# lighting_ctl.net
KiCad netlist of a schematic drawn in EAGLE
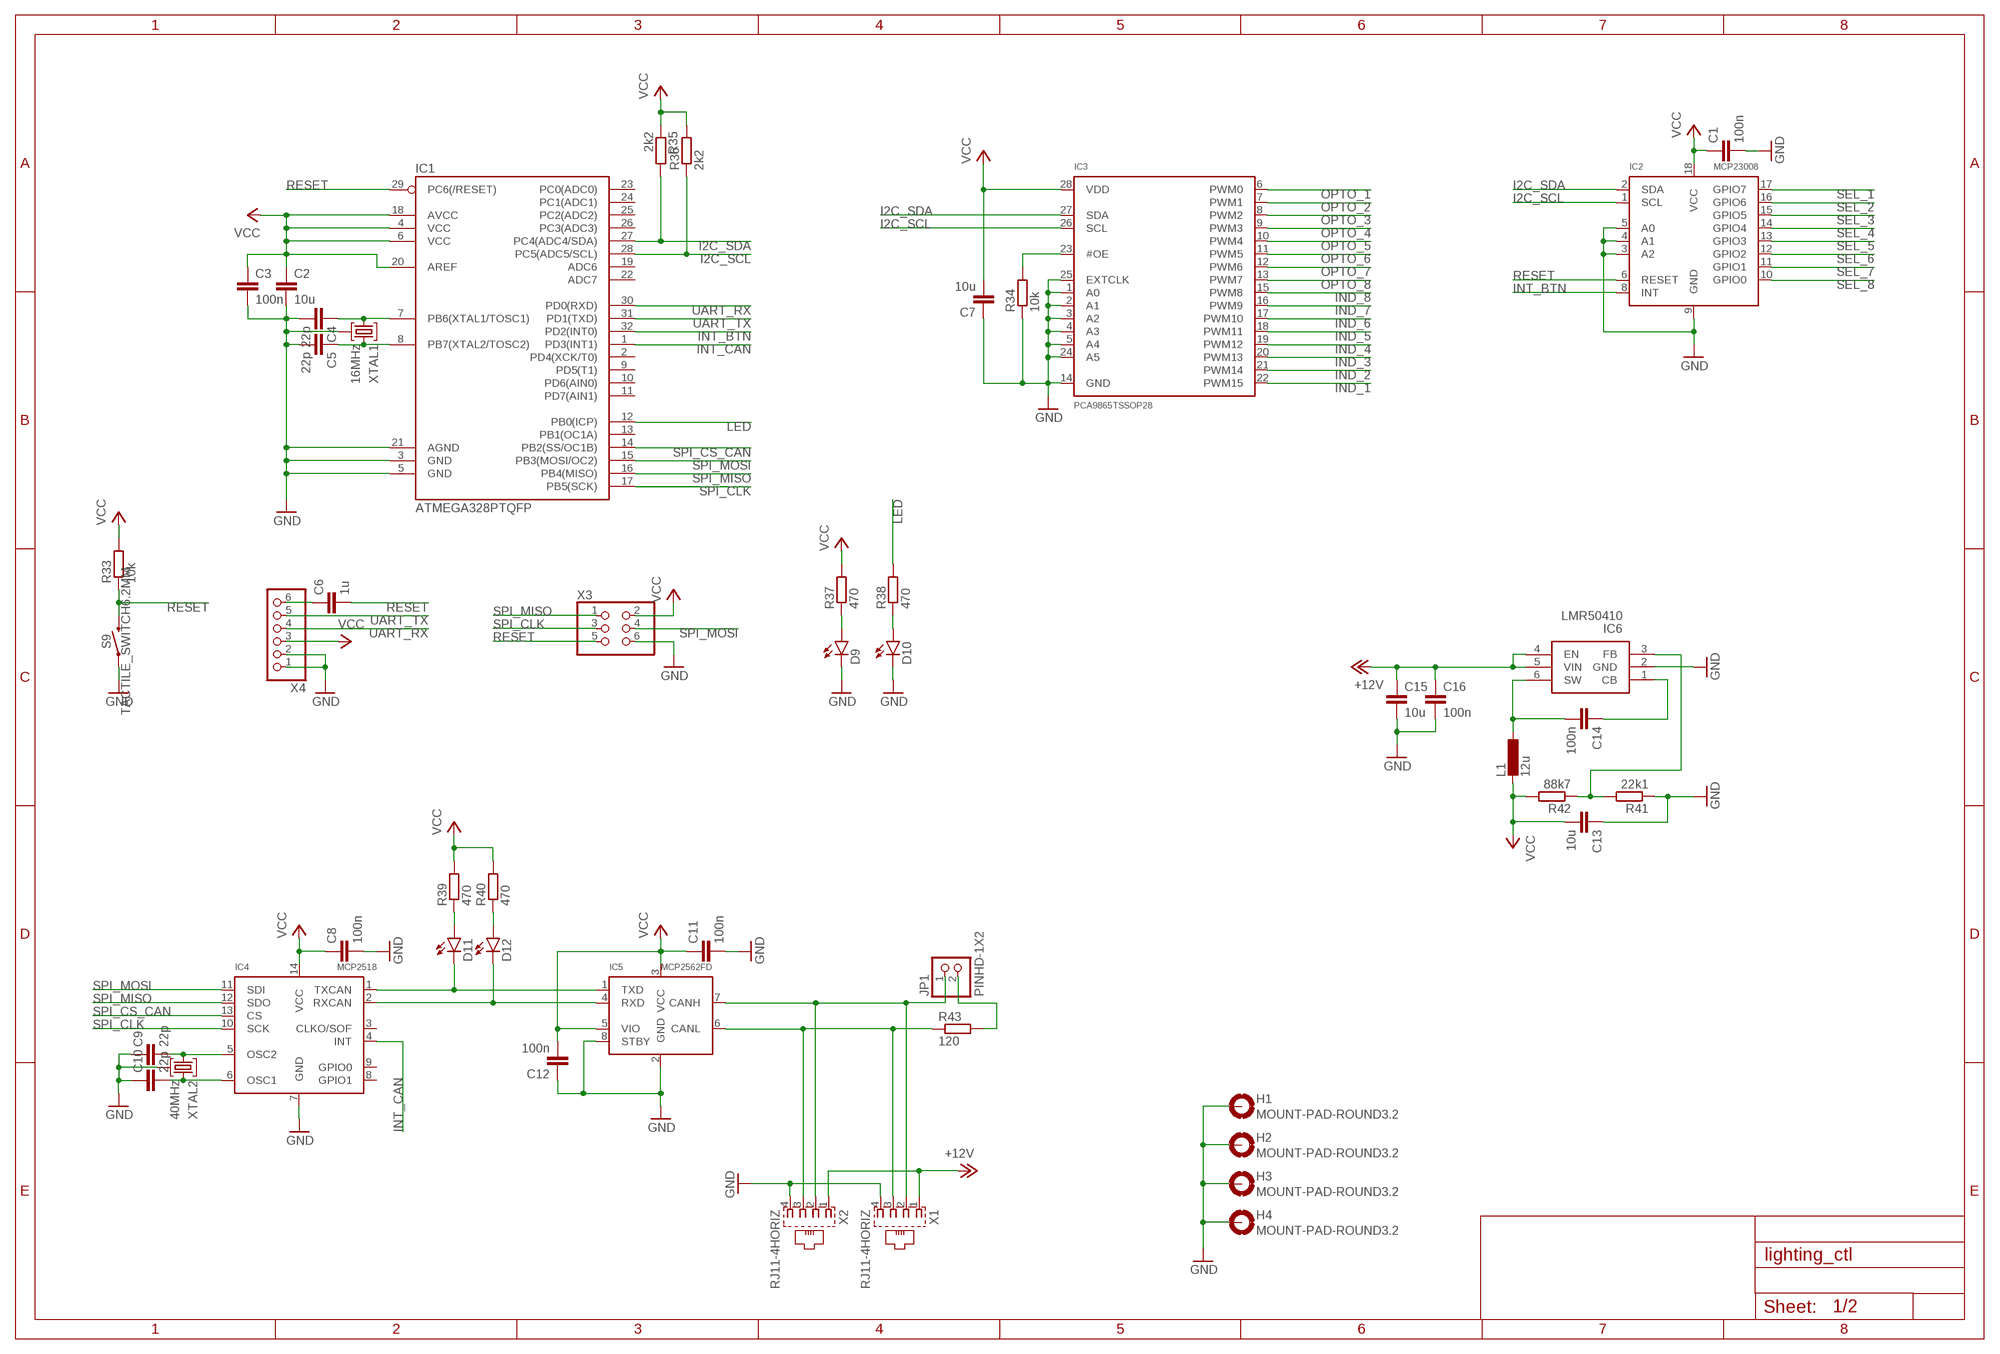
[diagram p0: schematic, sheet 1]
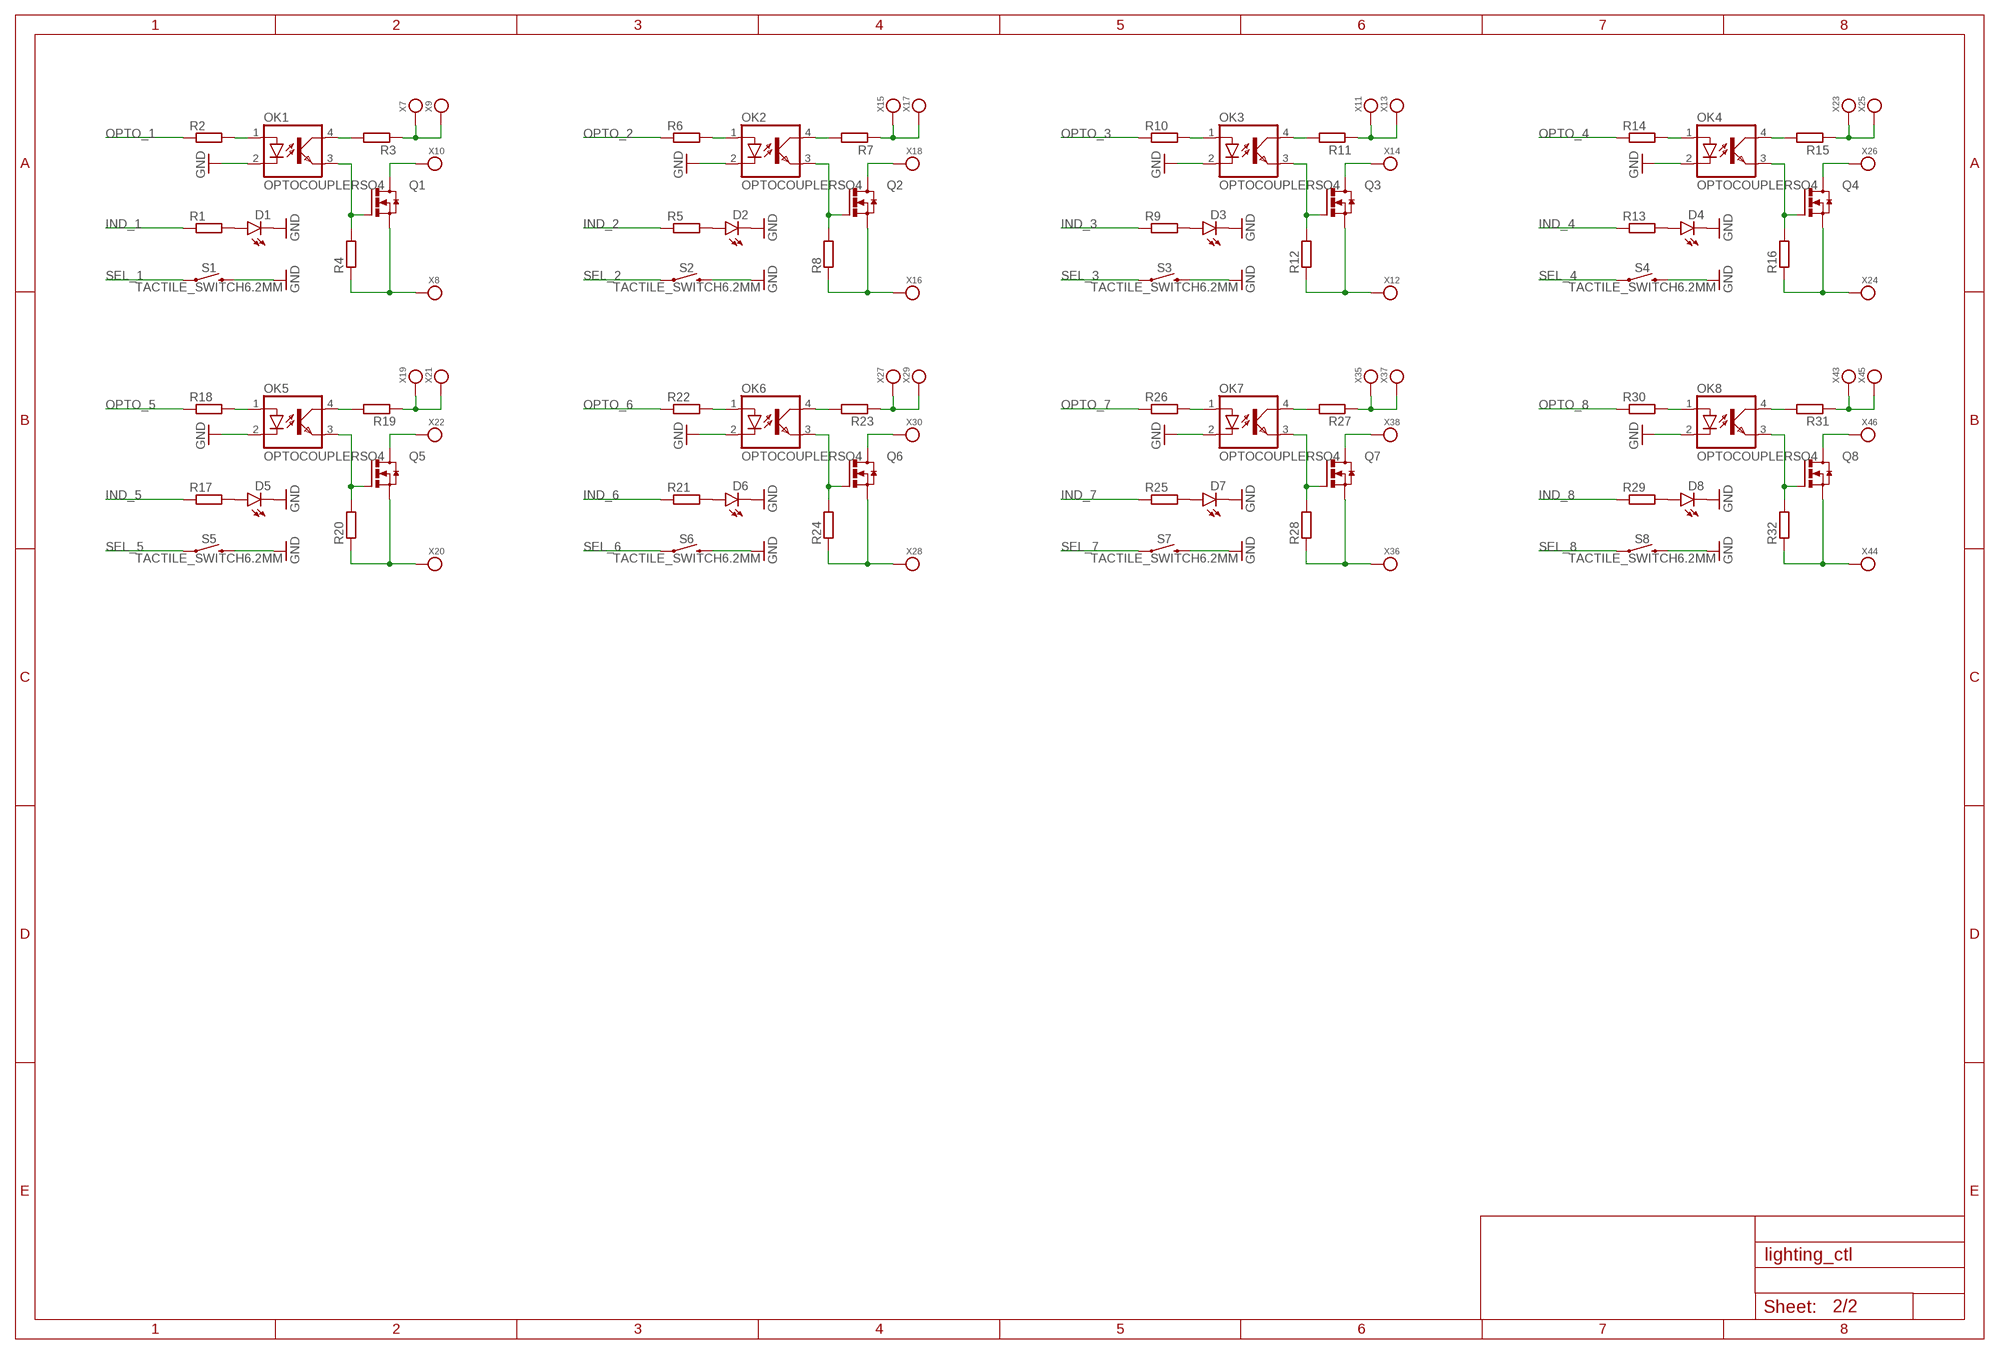
[diagram p1: schematic, sheet 2]

(export (version "E")
  (design (tool "Eeschema 10.0.6"))
  (components
    (comp (ref "D1")
      (value "LED1206")
      (footprint "eagle-import:CHIPLED_1206")
      (libsource (lib "eagle-import") (part "LED1206"))
    )
    (comp (ref "D2")
      (value "LED1206")
      (footprint "eagle-import:CHIPLED_1206")
      (libsource (lib "eagle-import") (part "LED1206"))
    )
    (comp (ref "D3")
      (value "LED1206")
      (footprint "eagle-import:CHIPLED_1206")
      (libsource (lib "eagle-import") (part "LED1206"))
    )
    (comp (ref "D4")
      (value "LED1206")
      (footprint "eagle-import:CHIPLED_1206")
      (libsource (lib "eagle-import") (part "LED1206"))
    )
    (comp (ref "D5")
      (value "LED1206")
      (footprint "eagle-import:CHIPLED_1206")
      (libsource (lib "eagle-import") (part "LED1206"))
    )
    (comp (ref "D6")
      (value "LED1206")
      (footprint "eagle-import:CHIPLED_1206")
      (libsource (lib "eagle-import") (part "LED1206"))
    )
    (comp (ref "D7")
      (value "LED1206")
      (footprint "eagle-import:CHIPLED_1206")
      (libsource (lib "eagle-import") (part "LED1206"))
    )
    (comp (ref "D8")
      (value "LED1206")
      (footprint "eagle-import:CHIPLED_1206")
      (libsource (lib "eagle-import") (part "LED1206"))
    )
    (comp (ref "OK1")
      (value "OPTOCOUPLERSO4")
      (footprint "eagle-import:SO04")
      (libsource (lib "eagle-import") (part "OPTOCOUPLERSO4"))
    )
    (comp (ref "OK2")
      (value "OPTOCOUPLERSO4")
      (footprint "eagle-import:SO04")
      (libsource (lib "eagle-import") (part "OPTOCOUPLERSO4"))
    )
    (comp (ref "OK3")
      (value "OPTOCOUPLERSO4")
      (footprint "eagle-import:SO04")
      (libsource (lib "eagle-import") (part "OPTOCOUPLERSO4"))
    )
    (comp (ref "OK4")
      (value "OPTOCOUPLERSO4")
      (footprint "eagle-import:SO04")
      (libsource (lib "eagle-import") (part "OPTOCOUPLERSO4"))
    )
    (comp (ref "OK5")
      (value "OPTOCOUPLERSO4")
      (footprint "eagle-import:SO04")
      (libsource (lib "eagle-import") (part "OPTOCOUPLERSO4"))
    )
    (comp (ref "OK6")
      (value "OPTOCOUPLERSO4")
      (footprint "eagle-import:SO04")
      (libsource (lib "eagle-import") (part "OPTOCOUPLERSO4"))
    )
    (comp (ref "OK7")
      (value "OPTOCOUPLERSO4")
      (footprint "eagle-import:SO04")
      (libsource (lib "eagle-import") (part "OPTOCOUPLERSO4"))
    )
    (comp (ref "OK8")
      (value "OPTOCOUPLERSO4")
      (footprint "eagle-import:SO04")
      (libsource (lib "eagle-import") (part "OPTOCOUPLERSO4"))
    )
    (comp (ref "Q1")
      (value "MOSFET_N_CHANNELSOT223")
      (footprint "eagle-import:SOT223")
      (libsource (lib "eagle-import") (part "MOSFET_N_CHANNELSOT223"))
    )
    (comp (ref "Q2")
      (value "MOSFET_N_CHANNELSOT223")
      (footprint "eagle-import:SOT223")
      (libsource (lib "eagle-import") (part "MOSFET_N_CHANNELSOT223"))
    )
    (comp (ref "Q3")
      (value "MOSFET_N_CHANNELSOT223")
      (footprint "eagle-import:SOT223")
      (libsource (lib "eagle-import") (part "MOSFET_N_CHANNELSOT223"))
    )
    (comp (ref "Q4")
      (value "MOSFET_N_CHANNELSOT223")
      (footprint "eagle-import:SOT223")
      (libsource (lib "eagle-import") (part "MOSFET_N_CHANNELSOT223"))
    )
    (comp (ref "Q5")
      (value "MOSFET_N_CHANNELSOT223")
      (footprint "eagle-import:SOT223")
      (libsource (lib "eagle-import") (part "MOSFET_N_CHANNELSOT223"))
    )
    (comp (ref "Q6")
      (value "MOSFET_N_CHANNELSOT223")
      (footprint "eagle-import:SOT223")
      (libsource (lib "eagle-import") (part "MOSFET_N_CHANNELSOT223"))
    )
    (comp (ref "Q7")
      (value "MOSFET_N_CHANNELSOT223")
      (footprint "eagle-import:SOT223")
      (libsource (lib "eagle-import") (part "MOSFET_N_CHANNELSOT223"))
    )
    (comp (ref "Q8")
      (value "MOSFET_N_CHANNELSOT223")
      (footprint "eagle-import:SOT223")
      (libsource (lib "eagle-import") (part "MOSFET_N_CHANNELSOT223"))
    )
    (comp (ref "R1")
      (value "RESISTOR0805")
      (footprint "eagle-import:R0805")
      (libsource (lib "eagle-import") (part "RESISTOR0805"))
    )
    (comp (ref "R2")
      (value "RESISTOR0805")
      (footprint "eagle-import:R0805")
      (libsource (lib "eagle-import") (part "RESISTOR0805"))
    )
    (comp (ref "R3")
      (value "RESISTOR0805")
      (footprint "eagle-import:R0805")
      (libsource (lib "eagle-import") (part "RESISTOR0805"))
    )
    (comp (ref "R4")
      (value "RESISTOR0805")
      (footprint "eagle-import:R0805")
      (libsource (lib "eagle-import") (part "RESISTOR0805"))
    )
    (comp (ref "R5")
      (value "RESISTOR0805")
      (footprint "eagle-import:R0805")
      (libsource (lib "eagle-import") (part "RESISTOR0805"))
    )
    (comp (ref "R6")
      (value "RESISTOR0805")
      (footprint "eagle-import:R0805")
      (libsource (lib "eagle-import") (part "RESISTOR0805"))
    )
    (comp (ref "R7")
      (value "RESISTOR0805")
      (footprint "eagle-import:R0805")
      (libsource (lib "eagle-import") (part "RESISTOR0805"))
    )
    (comp (ref "R8")
      (value "RESISTOR0805")
      (footprint "eagle-import:R0805")
      (libsource (lib "eagle-import") (part "RESISTOR0805"))
    )
    (comp (ref "R9")
      (value "RESISTOR0805")
      (footprint "eagle-import:R0805")
      (libsource (lib "eagle-import") (part "RESISTOR0805"))
    )
    (comp (ref "R10")
      (value "RESISTOR0805")
      (footprint "eagle-import:R0805")
      (libsource (lib "eagle-import") (part "RESISTOR0805"))
    )
    (comp (ref "R11")
      (value "RESISTOR0805")
      (footprint "eagle-import:R0805")
      (libsource (lib "eagle-import") (part "RESISTOR0805"))
    )
    (comp (ref "R12")
      (value "RESISTOR0805")
      (footprint "eagle-import:R0805")
      (libsource (lib "eagle-import") (part "RESISTOR0805"))
    )
    (comp (ref "R13")
      (value "RESISTOR0805")
      (footprint "eagle-import:R0805")
      (libsource (lib "eagle-import") (part "RESISTOR0805"))
    )
    (comp (ref "R14")
      (value "RESISTOR0805")
      (footprint "eagle-import:R0805")
      (libsource (lib "eagle-import") (part "RESISTOR0805"))
    )
    (comp (ref "R15")
      (value "RESISTOR0805")
      (footprint "eagle-import:R0805")
      (libsource (lib "eagle-import") (part "RESISTOR0805"))
    )
    (comp (ref "R16")
      (value "RESISTOR0805")
      (footprint "eagle-import:R0805")
      (libsource (lib "eagle-import") (part "RESISTOR0805"))
    )
    (comp (ref "R17")
      (value "RESISTOR0805")
      (footprint "eagle-import:R0805")
      (libsource (lib "eagle-import") (part "RESISTOR0805"))
    )
    (comp (ref "R18")
      (value "RESISTOR0805")
      (footprint "eagle-import:R0805")
      (libsource (lib "eagle-import") (part "RESISTOR0805"))
    )
    (comp (ref "R19")
      (value "RESISTOR0805")
      (footprint "eagle-import:R0805")
      (libsource (lib "eagle-import") (part "RESISTOR0805"))
    )
    (comp (ref "R20")
      (value "RESISTOR0805")
      (footprint "eagle-import:R0805")
      (libsource (lib "eagle-import") (part "RESISTOR0805"))
    )
    (comp (ref "R21")
      (value "RESISTOR0805")
      (footprint "eagle-import:R0805")
      (libsource (lib "eagle-import") (part "RESISTOR0805"))
    )
    (comp (ref "R22")
      (value "RESISTOR0805")
      (footprint "eagle-import:R0805")
      (libsource (lib "eagle-import") (part "RESISTOR0805"))
    )
    (comp (ref "R23")
      (value "RESISTOR0805")
      (footprint "eagle-import:R0805")
      (libsource (lib "eagle-import") (part "RESISTOR0805"))
    )
    (comp (ref "R24")
      (value "RESISTOR0805")
      (footprint "eagle-import:R0805")
      (libsource (lib "eagle-import") (part "RESISTOR0805"))
    )
    (comp (ref "R25")
      (value "RESISTOR0805")
      (footprint "eagle-import:R0805")
      (libsource (lib "eagle-import") (part "RESISTOR0805"))
    )
    (comp (ref "R26")
      (value "RESISTOR0805")
      (footprint "eagle-import:R0805")
      (libsource (lib "eagle-import") (part "RESISTOR0805"))
    )
    (comp (ref "R27")
      (value "RESISTOR0805")
      (footprint "eagle-import:R0805")
      (libsource (lib "eagle-import") (part "RESISTOR0805"))
    )
    (comp (ref "R28")
      (value "RESISTOR0805")
      (footprint "eagle-import:R0805")
      (libsource (lib "eagle-import") (part "RESISTOR0805"))
    )
    (comp (ref "R29")
      (value "RESISTOR0805")
      (footprint "eagle-import:R0805")
      (libsource (lib "eagle-import") (part "RESISTOR0805"))
    )
    (comp (ref "R30")
      (value "RESISTOR0805")
      (footprint "eagle-import:R0805")
      (libsource (lib "eagle-import") (part "RESISTOR0805"))
    )
    (comp (ref "R31")
      (value "RESISTOR0805")
      (footprint "eagle-import:R0805")
      (libsource (lib "eagle-import") (part "RESISTOR0805"))
    )
    (comp (ref "R32")
      (value "RESISTOR0805")
      (footprint "eagle-import:R0805")
      (libsource (lib "eagle-import") (part "RESISTOR0805"))
    )
    (comp (ref "S1")
      (value "TACTILE_SWITCH6.2MM")
      (footprint "eagle-import:TACTILE_SWITCH_SMD_6.2MM")
      (libsource (lib "eagle-import") (part "TACTILE_SWITCH6.2MM"))
    )
    (comp (ref "S2")
      (value "TACTILE_SWITCH6.2MM")
      (footprint "eagle-import:TACTILE_SWITCH_SMD_6.2MM")
      (libsource (lib "eagle-import") (part "TACTILE_SWITCH6.2MM"))
    )
    (comp (ref "S3")
      (value "TACTILE_SWITCH6.2MM")
      (footprint "eagle-import:TACTILE_SWITCH_SMD_6.2MM")
      (libsource (lib "eagle-import") (part "TACTILE_SWITCH6.2MM"))
    )
    (comp (ref "S4")
      (value "TACTILE_SWITCH6.2MM")
      (footprint "eagle-import:TACTILE_SWITCH_SMD_6.2MM")
      (libsource (lib "eagle-import") (part "TACTILE_SWITCH6.2MM"))
    )
    (comp (ref "S5")
      (value "TACTILE_SWITCH6.2MM")
      (footprint "eagle-import:TACTILE_SWITCH_SMD_6.2MM")
      (libsource (lib "eagle-import") (part "TACTILE_SWITCH6.2MM"))
    )
    (comp (ref "S6")
      (value "TACTILE_SWITCH6.2MM")
      (footprint "eagle-import:TACTILE_SWITCH_SMD_6.2MM")
      (libsource (lib "eagle-import") (part "TACTILE_SWITCH6.2MM"))
    )
    (comp (ref "S7")
      (value "TACTILE_SWITCH6.2MM")
      (footprint "eagle-import:TACTILE_SWITCH_SMD_6.2MM")
      (libsource (lib "eagle-import") (part "TACTILE_SWITCH6.2MM"))
    )
    (comp (ref "S8")
      (value "TACTILE_SWITCH6.2MM")
      (footprint "eagle-import:TACTILE_SWITCH_SMD_6.2MM")
      (libsource (lib "eagle-import") (part "TACTILE_SWITCH6.2MM"))
    )
    (comp (ref "X7")
      (value "KEYSTONE_7788")
      (footprint "eagle-import:KEYSTONE_7788")
      (libsource (lib "eagle-import") (part "KEYSTONE_7788"))
    )
    (comp (ref "X8")
      (value "KEYSTONE_7788")
      (footprint "eagle-import:KEYSTONE_7788")
      (libsource (lib "eagle-import") (part "KEYSTONE_7788"))
    )
    (comp (ref "X9")
      (value "KEYSTONE_7788")
      (footprint "eagle-import:KEYSTONE_7788")
      (libsource (lib "eagle-import") (part "KEYSTONE_7788"))
    )
    (comp (ref "X10")
      (value "KEYSTONE_7788")
      (footprint "eagle-import:KEYSTONE_7788")
      (libsource (lib "eagle-import") (part "KEYSTONE_7788"))
    )
    (comp (ref "X11")
      (value "KEYSTONE_7788")
      (footprint "eagle-import:KEYSTONE_7788")
      (libsource (lib "eagle-import") (part "KEYSTONE_7788"))
    )
    (comp (ref "X12")
      (value "KEYSTONE_7788")
      (footprint "eagle-import:KEYSTONE_7788")
      (libsource (lib "eagle-import") (part "KEYSTONE_7788"))
    )
    (comp (ref "X13")
      (value "KEYSTONE_7788")
      (footprint "eagle-import:KEYSTONE_7788")
      (libsource (lib "eagle-import") (part "KEYSTONE_7788"))
    )
    (comp (ref "X14")
      (value "KEYSTONE_7788")
      (footprint "eagle-import:KEYSTONE_7788")
      (libsource (lib "eagle-import") (part "KEYSTONE_7788"))
    )
    (comp (ref "X15")
      (value "KEYSTONE_7788")
      (footprint "eagle-import:KEYSTONE_7788")
      (libsource (lib "eagle-import") (part "KEYSTONE_7788"))
    )
    (comp (ref "X16")
      (value "KEYSTONE_7788")
      (footprint "eagle-import:KEYSTONE_7788")
      (libsource (lib "eagle-import") (part "KEYSTONE_7788"))
    )
    (comp (ref "X17")
      (value "KEYSTONE_7788")
      (footprint "eagle-import:KEYSTONE_7788")
      (libsource (lib "eagle-import") (part "KEYSTONE_7788"))
    )
    (comp (ref "X18")
      (value "KEYSTONE_7788")
      (footprint "eagle-import:KEYSTONE_7788")
      (libsource (lib "eagle-import") (part "KEYSTONE_7788"))
    )
    (comp (ref "X19")
      (value "KEYSTONE_7788")
      (footprint "eagle-import:KEYSTONE_7788")
      (libsource (lib "eagle-import") (part "KEYSTONE_7788"))
    )
    (comp (ref "X20")
      (value "KEYSTONE_7788")
      (footprint "eagle-import:KEYSTONE_7788")
      (libsource (lib "eagle-import") (part "KEYSTONE_7788"))
    )
    (comp (ref "X21")
      (value "KEYSTONE_7788")
      (footprint "eagle-import:KEYSTONE_7788")
      (libsource (lib "eagle-import") (part "KEYSTONE_7788"))
    )
    (comp (ref "X22")
      (value "KEYSTONE_7788")
      (footprint "eagle-import:KEYSTONE_7788")
      (libsource (lib "eagle-import") (part "KEYSTONE_7788"))
    )
    (comp (ref "X23")
      (value "KEYSTONE_7788")
      (footprint "eagle-import:KEYSTONE_7788")
      (libsource (lib "eagle-import") (part "KEYSTONE_7788"))
    )
    (comp (ref "X24")
      (value "KEYSTONE_7788")
      (footprint "eagle-import:KEYSTONE_7788")
      (libsource (lib "eagle-import") (part "KEYSTONE_7788"))
    )
    (comp (ref "X25")
      (value "KEYSTONE_7788")
      (footprint "eagle-import:KEYSTONE_7788")
      (libsource (lib "eagle-import") (part "KEYSTONE_7788"))
    )
    (comp (ref "X26")
      (value "KEYSTONE_7788")
      (footprint "eagle-import:KEYSTONE_7788")
      (libsource (lib "eagle-import") (part "KEYSTONE_7788"))
    )
    (comp (ref "X27")
      (value "KEYSTONE_7788")
      (footprint "eagle-import:KEYSTONE_7788")
      (libsource (lib "eagle-import") (part "KEYSTONE_7788"))
    )
    (comp (ref "X28")
      (value "KEYSTONE_7788")
      (footprint "eagle-import:KEYSTONE_7788")
      (libsource (lib "eagle-import") (part "KEYSTONE_7788"))
    )
    (comp (ref "X29")
      (value "KEYSTONE_7788")
      (footprint "eagle-import:KEYSTONE_7788")
      (libsource (lib "eagle-import") (part "KEYSTONE_7788"))
    )
    (comp (ref "X30")
      (value "KEYSTONE_7788")
      (footprint "eagle-import:KEYSTONE_7788")
      (libsource (lib "eagle-import") (part "KEYSTONE_7788"))
    )
    (comp (ref "X35")
      (value "KEYSTONE_7788")
      (footprint "eagle-import:KEYSTONE_7788")
      (libsource (lib "eagle-import") (part "KEYSTONE_7788"))
    )
    (comp (ref "X36")
      (value "KEYSTONE_7788")
      (footprint "eagle-import:KEYSTONE_7788")
      (libsource (lib "eagle-import") (part "KEYSTONE_7788"))
    )
    (comp (ref "X37")
      (value "KEYSTONE_7788")
      (footprint "eagle-import:KEYSTONE_7788")
      (libsource (lib "eagle-import") (part "KEYSTONE_7788"))
    )
    (comp (ref "X38")
      (value "KEYSTONE_7788")
      (footprint "eagle-import:KEYSTONE_7788")
      (libsource (lib "eagle-import") (part "KEYSTONE_7788"))
    )
    (comp (ref "X43")
      (value "KEYSTONE_7788")
      (footprint "eagle-import:KEYSTONE_7788")
      (libsource (lib "eagle-import") (part "KEYSTONE_7788"))
    )
    (comp (ref "X44")
      (value "KEYSTONE_7788")
      (footprint "eagle-import:KEYSTONE_7788")
      (libsource (lib "eagle-import") (part "KEYSTONE_7788"))
    )
    (comp (ref "X45")
      (value "KEYSTONE_7788")
      (footprint "eagle-import:KEYSTONE_7788")
      (libsource (lib "eagle-import") (part "KEYSTONE_7788"))
    )
    (comp (ref "X46")
      (value "KEYSTONE_7788")
      (footprint "eagle-import:KEYSTONE_7788")
      (libsource (lib "eagle-import") (part "KEYSTONE_7788"))
    )
    (comp (ref "C1")
      (value "100n")
      (footprint "eagle-import:C0805")
      (libsource (lib "eagle-import") (part "CAPACITOR0805"))
    )
    (comp (ref "C2")
      (value "10u")
      (footprint "eagle-import:C1206")
      (libsource (lib "eagle-import") (part "CAPACITOR1206"))
    )
    (comp (ref "C3")
      (value "100n")
      (footprint "eagle-import:C0805")
      (libsource (lib "eagle-import") (part "CAPACITOR0805"))
    )
    (comp (ref "C4")
      (value "22p")
      (footprint "eagle-import:C0805")
      (libsource (lib "eagle-import") (part "CAPACITOR0805"))
    )
    (comp (ref "C5")
      (value "22p")
      (footprint "eagle-import:C0805")
      (libsource (lib "eagle-import") (part "CAPACITOR0805"))
    )
    (comp (ref "C6")
      (value "1u")
      (footprint "eagle-import:C0805")
      (libsource (lib "eagle-import") (part "CAPACITOR0805"))
    )
    (comp (ref "C7")
      (value "10u")
      (footprint "eagle-import:C1206")
      (libsource (lib "eagle-import") (part "CAPACITOR1206"))
    )
    (comp (ref "C8")
      (value "100n")
      (footprint "eagle-import:C0805")
      (libsource (lib "eagle-import") (part "CAPACITOR0805"))
    )
    (comp (ref "C9")
      (value "22p")
      (footprint "eagle-import:C0805")
      (libsource (lib "eagle-import") (part "CAPACITOR0805"))
    )
    (comp (ref "C10")
      (value "22p")
      (footprint "eagle-import:C0805")
      (libsource (lib "eagle-import") (part "CAPACITOR0805"))
    )
    (comp (ref "C11")
      (value "100n")
      (footprint "eagle-import:C0805")
      (libsource (lib "eagle-import") (part "CAPACITOR0805"))
    )
    (comp (ref "C12")
      (value "100n")
      (footprint "eagle-import:C0805")
      (libsource (lib "eagle-import") (part "CAPACITOR0805"))
    )
    (comp (ref "C13")
      (value "10u")
      (footprint "eagle-import:C1206")
      (libsource (lib "eagle-import") (part "CAPACITOR1206"))
    )
    (comp (ref "C14")
      (value "100n")
      (footprint "eagle-import:C0805")
      (libsource (lib "eagle-import") (part "CAPACITOR0805"))
    )
    (comp (ref "C15")
      (value "10u")
      (footprint "eagle-import:C1206")
      (libsource (lib "eagle-import") (part "CAPACITOR1206"))
    )
    (comp (ref "C16")
      (value "100n")
      (footprint "eagle-import:C0805")
      (libsource (lib "eagle-import") (part "CAPACITOR0805"))
    )
    (comp (ref "D9")
      (value "LED1206")
      (footprint "eagle-import:CHIPLED_1206")
      (libsource (lib "eagle-import") (part "LED1206"))
    )
    (comp (ref "D10")
      (value "LED1206")
      (footprint "eagle-import:CHIPLED_1206")
      (libsource (lib "eagle-import") (part "LED1206"))
    )
    (comp (ref "D11")
      (value "LED1206")
      (footprint "eagle-import:CHIPLED_1206")
      (libsource (lib "eagle-import") (part "LED1206"))
    )
    (comp (ref "D12")
      (value "LED1206")
      (footprint "eagle-import:CHIPLED_1206")
      (libsource (lib "eagle-import") (part "LED1206"))
    )
    (comp (ref "H1")
      (value "MOUNT-PAD-ROUND3.2")
      (footprint "eagle-import:3,2-PAD")
      (libsource (lib "eagle-import") (part "MOUNT-PAD-ROUND3.2"))
    )
    (comp (ref "H2")
      (value "MOUNT-PAD-ROUND3.2")
      (footprint "eagle-import:3,2-PAD")
      (libsource (lib "eagle-import") (part "MOUNT-PAD-ROUND3.2"))
    )
    (comp (ref "H3")
      (value "MOUNT-PAD-ROUND3.2")
      (footprint "eagle-import:3,2-PAD")
      (libsource (lib "eagle-import") (part "MOUNT-PAD-ROUND3.2"))
    )
    (comp (ref "H4")
      (value "MOUNT-PAD-ROUND3.2")
      (footprint "eagle-import:3,2-PAD")
      (libsource (lib "eagle-import") (part "MOUNT-PAD-ROUND3.2"))
    )
    (comp (ref "IC1")
      (value "ATMEGA328PTQFP")
      (footprint "eagle-import:TQFP32_0.8MM_7X7MM")
      (libsource (lib "eagle-import") (part "ATMEGA328PTQFP"))
    )
    (comp (ref "IC2")
      (value "MCP23008")
      (footprint "eagle-import:SO18W")
      (libsource (lib "eagle-import") (part "MCP23008SO18W"))
    )
    (comp (ref "IC3")
      (value "PCA9865TSSOP28")
      (footprint "eagle-import:TSSOP28")
      (libsource (lib "eagle-import") (part "PCA9865TSSOP28"))
    )
    (comp (ref "IC4")
      (value "MCP2518")
      (footprint "eagle-import:SO14")
      (libsource (lib "eagle-import") (part "MCP2518FDSO14"))
    )
    (comp (ref "IC5")
      (value "MCP2562FD")
      (footprint "eagle-import:SO08")
      (libsource (lib "eagle-import") (part "MCP2562FDSO08"))
    )
    (comp (ref "IC6")
      (value "LMR50410")
      (footprint "eagle-import:SOT23-6")
      (libsource (lib "eagle-import") (part "LMR50410"))
    )
    (comp (ref "JP1")
      (value "PINHD-1X2")
      (footprint "eagle-import:1X02")
      (libsource (lib "eagle-import") (part "PINHD-1X2"))
    )
    (comp (ref "L1")
      (value "12u")
      (footprint "eagle-import:L_7.3MM")
      (libsource (lib "eagle-import") (part "INDUCTOR7.3MM"))
    )
    (comp (ref "R33")
      (value "10k")
      (footprint "eagle-import:R0805")
      (libsource (lib "eagle-import") (part "RESISTOR0805"))
    )
    (comp (ref "R34")
      (value "10k")
      (footprint "eagle-import:R0805")
      (libsource (lib "eagle-import") (part "RESISTOR0805"))
    )
    (comp (ref "R35")
      (value "2k2")
      (footprint "eagle-import:R0805")
      (libsource (lib "eagle-import") (part "RESISTOR0805"))
    )
    (comp (ref "R36")
      (value "2k2")
      (footprint "eagle-import:R0805")
      (libsource (lib "eagle-import") (part "RESISTOR0805"))
    )
    (comp (ref "R37")
      (value "470")
      (footprint "eagle-import:R0805")
      (libsource (lib "eagle-import") (part "RESISTOR0805"))
    )
    (comp (ref "R38")
      (value "470")
      (footprint "eagle-import:R0805")
      (libsource (lib "eagle-import") (part "RESISTOR0805"))
    )
    (comp (ref "R39")
      (value "470")
      (footprint "eagle-import:R0805")
      (libsource (lib "eagle-import") (part "RESISTOR0805"))
    )
    (comp (ref "R40")
      (value "470")
      (footprint "eagle-import:R0805")
      (libsource (lib "eagle-import") (part "RESISTOR0805"))
    )
    (comp (ref "R41")
      (value "22k1")
      (footprint "eagle-import:R0805")
      (libsource (lib "eagle-import") (part "RESISTOR0805"))
    )
    (comp (ref "R42")
      (value "88k7")
      (footprint "eagle-import:R0805")
      (libsource (lib "eagle-import") (part "RESISTOR0805"))
    )
    (comp (ref "R43")
      (value "120")
      (footprint "eagle-import:R0805")
      (libsource (lib "eagle-import") (part "RESISTOR0805"))
    )
    (comp (ref "S9")
      (value "TACTILE_SWITCH6.2MM")
      (footprint "eagle-import:TACTILE_SWITCH_SMD_6.2MM")
      (libsource (lib "eagle-import") (part "TACTILE_SWITCH6.2MM"))
    )
    (comp (ref "X1")
      (value "RJ11-4HORIZ")
      (footprint "eagle-import:RJ11-4_HORIZ")
      (libsource (lib "eagle-import") (part "RJ11-4HORIZ"))
    )
    (comp (ref "X2")
      (value "RJ11-4HORIZ")
      (footprint "eagle-import:RJ11-4_HORIZ")
      (libsource (lib "eagle-import") (part "RJ11-4HORIZ"))
    )
    (comp (ref "X3")
      (value "PINHD-2X3")
      (footprint "eagle-import:2X03")
      (libsource (lib "eagle-import") (part "PINHD-2X3"))
    )
    (comp (ref "X4")
      (value "PINHD-1X6")
      (footprint "eagle-import:1X06")
      (libsource (lib "eagle-import") (part "PINHD-1X6"))
    )
    (comp (ref "XTAL1")
      (value "16MHz")
      (footprint "eagle-import:XTAL_5.0X3.2_4")
      (libsource (lib "eagle-import") (part "CRYSTAL_GND5X3.2"))
    )
    (comp (ref "XTAL2")
      (value "40MHz")
      (footprint "eagle-import:XTAL_5.0X3.2_4")
      (libsource (lib "eagle-import") (part "CRYSTAL_GND5X3.2"))
    )
  )
  (nets
    (net (code "1") (name "+12V") (class "Default")
      (node (ref "C15") (pin "1") (pinfunction "1_1") (pintype "passive"))
      (node (ref "C16") (pin "1") (pinfunction "1_1") (pintype "passive"))
      (node (ref "IC6") (pin "4") (pinfunction "EN_4") (pintype "bidirectional"))
      (node (ref "IC6") (pin "5") (pinfunction "VIN_5") (pintype "bidirectional"))
      (node (ref "X1") (pin "1") (pinfunction "1_1") (pintype "passive"))
      (node (ref "X2") (pin "1") (pinfunction "1_1") (pintype "passive"))
    )
    (net (code "2") (name "GND") (class "Default")
      (node (ref "C1") (pin "2") (pinfunction "2_2") (pintype "passive"))
      (node (ref "C10") (pin "1") (pinfunction "1_1") (pintype "passive"))
      (node (ref "C11") (pin "2") (pinfunction "2_2") (pintype "passive"))
      (node (ref "C12") (pin "1") (pinfunction "1_1") (pintype "passive"))
      (node (ref "C13") (pin "1") (pinfunction "1_1") (pintype "passive"))
      (node (ref "C15") (pin "2") (pinfunction "2_2") (pintype "passive"))
      (node (ref "C16") (pin "2") (pinfunction "2_2") (pintype "passive"))
      (node (ref "C2") (pin "2") (pinfunction "2_2") (pintype "passive"))
      (node (ref "C3") (pin "2") (pinfunction "2_2") (pintype "passive"))
      (node (ref "C4") (pin "2") (pinfunction "2_2") (pintype "passive"))
      (node (ref "C5") (pin "2") (pinfunction "2_2") (pintype "passive"))
      (node (ref "C7") (pin "1") (pinfunction "1_1") (pintype "passive"))
      (node (ref "C8") (pin "2") (pinfunction "2_2") (pintype "passive"))
      (node (ref "C9") (pin "1") (pinfunction "1_1") (pintype "passive"))
      (node (ref "D1") (pin "C") (pinfunction "C_C") (pintype "passive"))
      (node (ref "D10") (pin "C") (pinfunction "C_C") (pintype "passive"))
      (node (ref "D2") (pin "C") (pinfunction "C_C") (pintype "passive"))
      (node (ref "D3") (pin "C") (pinfunction "C_C") (pintype "passive"))
      (node (ref "D4") (pin "C") (pinfunction "C_C") (pintype "passive"))
      (node (ref "D5") (pin "C") (pinfunction "C_C") (pintype "passive"))
      (node (ref "D6") (pin "C") (pinfunction "C_C") (pintype "passive"))
      (node (ref "D7") (pin "C") (pinfunction "C_C") (pintype "passive"))
      (node (ref "D8") (pin "C") (pinfunction "C_C") (pintype "passive"))
      (node (ref "D9") (pin "C") (pinfunction "C_C") (pintype "passive"))
      (node (ref "H1") (pin "B3,2") (pinfunction "MOUNT_B3,2") (pintype "passive"))
      (node (ref "H1") (pin "P$1") (pinfunction "MOUNT_P$1") (pintype "passive"))
      (node (ref "H1") (pin "P$2") (pinfunction "MOUNT_P$2") (pintype "passive"))
      (node (ref "H1") (pin "P$3") (pinfunction "MOUNT_P$3") (pintype "passive"))
      (node (ref "H1") (pin "P$4") (pinfunction "MOUNT_P$4") (pintype "passive"))
      (node (ref "H1") (pin "P$5") (pinfunction "MOUNT_P$5") (pintype "passive"))
      (node (ref "H1") (pin "P$6") (pinfunction "MOUNT_P$6") (pintype "passive"))
      (node (ref "H1") (pin "P$7") (pinfunction "MOUNT_P$7") (pintype "passive"))
      (node (ref "H1") (pin "P$8") (pinfunction "MOUNT_P$8") (pintype "passive"))
      (node (ref "H2") (pin "B3,2") (pinfunction "MOUNT_B3,2") (pintype "passive"))
      (node (ref "H2") (pin "P$1") (pinfunction "MOUNT_P$1") (pintype "passive"))
      (node (ref "H2") (pin "P$2") (pinfunction "MOUNT_P$2") (pintype "passive"))
      (node (ref "H2") (pin "P$3") (pinfunction "MOUNT_P$3") (pintype "passive"))
      (node (ref "H2") (pin "P$4") (pinfunction "MOUNT_P$4") (pintype "passive"))
      (node (ref "H2") (pin "P$5") (pinfunction "MOUNT_P$5") (pintype "passive"))
      (node (ref "H2") (pin "P$6") (pinfunction "MOUNT_P$6") (pintype "passive"))
      (node (ref "H2") (pin "P$7") (pinfunction "MOUNT_P$7") (pintype "passive"))
      (node (ref "H2") (pin "P$8") (pinfunction "MOUNT_P$8") (pintype "passive"))
      (node (ref "H3") (pin "B3,2") (pinfunction "MOUNT_B3,2") (pintype "passive"))
      (node (ref "H3") (pin "P$1") (pinfunction "MOUNT_P$1") (pintype "passive"))
      (node (ref "H3") (pin "P$2") (pinfunction "MOUNT_P$2") (pintype "passive"))
      (node (ref "H3") (pin "P$3") (pinfunction "MOUNT_P$3") (pintype "passive"))
      (node (ref "H3") (pin "P$4") (pinfunction "MOUNT_P$4") (pintype "passive"))
      (node (ref "H3") (pin "P$5") (pinfunction "MOUNT_P$5") (pintype "passive"))
      (node (ref "H3") (pin "P$6") (pinfunction "MOUNT_P$6") (pintype "passive"))
      (node (ref "H3") (pin "P$7") (pinfunction "MOUNT_P$7") (pintype "passive"))
      (node (ref "H3") (pin "P$8") (pinfunction "MOUNT_P$8") (pintype "passive"))
      (node (ref "H4") (pin "B3,2") (pinfunction "MOUNT_B3,2") (pintype "passive"))
      (node (ref "H4") (pin "P$1") (pinfunction "MOUNT_P$1") (pintype "passive"))
      (node (ref "H4") (pin "P$2") (pinfunction "MOUNT_P$2") (pintype "passive"))
      (node (ref "H4") (pin "P$3") (pinfunction "MOUNT_P$3") (pintype "passive"))
      (node (ref "H4") (pin "P$4") (pinfunction "MOUNT_P$4") (pintype "passive"))
      (node (ref "H4") (pin "P$5") (pinfunction "MOUNT_P$5") (pintype "passive"))
      (node (ref "H4") (pin "P$6") (pinfunction "MOUNT_P$6") (pintype "passive"))
      (node (ref "H4") (pin "P$7") (pinfunction "MOUNT_P$7") (pintype "passive"))
      (node (ref "H4") (pin "P$8") (pinfunction "MOUNT_P$8") (pintype "passive"))
      (node (ref "IC1") (pin "21") (pinfunction "AGND_21") (pintype "bidirectional"))
      (node (ref "IC1") (pin "3") (pinfunction "GND_3") (pintype "bidirectional"))
      (node (ref "IC1") (pin "5") (pinfunction "GND_5") (pintype "bidirectional"))
      (node (ref "IC2") (pin "3") (pinfunction "A2_3") (pintype "bidirectional"))
      (node (ref "IC2") (pin "4") (pinfunction "A1_4") (pintype "bidirectional"))
      (node (ref "IC2") (pin "5") (pinfunction "A0_5") (pintype "bidirectional"))
      (node (ref "IC2") (pin "9") (pinfunction "GND_9") (pintype "bidirectional"))
      (node (ref "IC3") (pin "1") (pinfunction "A0_1") (pintype "bidirectional"))
      (node (ref "IC3") (pin "14") (pinfunction "GND_14") (pintype "power_in"))
      (node (ref "IC3") (pin "2") (pinfunction "A1_2") (pintype "bidirectional"))
      (node (ref "IC3") (pin "24") (pinfunction "A5_24") (pintype "bidirectional"))
      (node (ref "IC3") (pin "25") (pinfunction "EXTCLK_25") (pintype "input"))
      (node (ref "IC3") (pin "3") (pinfunction "A2_3") (pintype "bidirectional"))
      (node (ref "IC3") (pin "4") (pinfunction "A3_4") (pintype "bidirectional"))
      (node (ref "IC3") (pin "5") (pinfunction "A4_5") (pintype "bidirectional"))
      (node (ref "IC4") (pin "7") (pinfunction "GND_7") (pintype "bidirectional"))
      (node (ref "IC5") (pin "2") (pinfunction "GND_2") (pintype "bidirectional"))
      (node (ref "IC5") (pin "8") (pinfunction "STBY_8") (pintype "bidirectional"))
      (node (ref "IC6") (pin "2") (pinfunction "GND_2") (pintype "bidirectional"))
      (node (ref "OK1") (pin "2") (pinfunction "C_2") (pintype "passive"))
      (node (ref "OK2") (pin "2") (pinfunction "C_2") (pintype "passive"))
      (node (ref "OK3") (pin "2") (pinfunction "C_2") (pintype "passive"))
      (node (ref "OK4") (pin "2") (pinfunction "C_2") (pintype "passive"))
      (node (ref "OK5") (pin "2") (pinfunction "C_2") (pintype "passive"))
      (node (ref "OK6") (pin "2") (pinfunction "C_2") (pintype "passive"))
      (node (ref "OK7") (pin "2") (pinfunction "C_2") (pintype "passive"))
      (node (ref "OK8") (pin "2") (pinfunction "C_2") (pintype "passive"))
      (node (ref "R34") (pin "1") (pinfunction "1_1") (pintype "passive"))
      (node (ref "R41") (pin "1") (pinfunction "1_1") (pintype "passive"))
      (node (ref "S1") (pin "B1") (pinfunction "2_B1") (pintype "passive"))
      (node (ref "S1") (pin "B2") (pinfunction "2_B2") (pintype "passive"))
      (node (ref "S2") (pin "B1") (pinfunction "2_B1") (pintype "passive"))
      (node (ref "S2") (pin "B2") (pinfunction "2_B2") (pintype "passive"))
      (node (ref "S3") (pin "B1") (pinfunction "2_B1") (pintype "passive"))
      (node (ref "S3") (pin "B2") (pinfunction "2_B2") (pintype "passive"))
      (node (ref "S4") (pin "B1") (pinfunction "2_B1") (pintype "passive"))
      (node (ref "S4") (pin "B2") (pinfunction "2_B2") (pintype "passive"))
      (node (ref "S5") (pin "B1") (pinfunction "2_B1") (pintype "passive"))
      (node (ref "S5") (pin "B2") (pinfunction "2_B2") (pintype "passive"))
      (node (ref "S6") (pin "B1") (pinfunction "2_B1") (pintype "passive"))
      (node (ref "S6") (pin "B2") (pinfunction "2_B2") (pintype "passive"))
      (node (ref "S7") (pin "B1") (pinfunction "2_B1") (pintype "passive"))
      (node (ref "S7") (pin "B2") (pinfunction "2_B2") (pintype "passive"))
      (node (ref "S8") (pin "B1") (pinfunction "2_B1") (pintype "passive"))
      (node (ref "S8") (pin "B2") (pinfunction "2_B2") (pintype "passive"))
      (node (ref "S9") (pin "A1") (pinfunction "1_A1") (pintype "passive"))
      (node (ref "S9") (pin "A2") (pinfunction "1_A2") (pintype "passive"))
      (node (ref "X1") (pin "4") (pinfunction "4_4") (pintype "passive"))
      (node (ref "X2") (pin "4") (pinfunction "4_4") (pintype "passive"))
      (node (ref "X3") (pin "6") (pinfunction "6_6") (pintype "passive"))
      (node (ref "X4") (pin "1") (pinfunction "1_1") (pintype "passive"))
      (node (ref "X4") (pin "2") (pinfunction "2_2") (pintype "passive"))
      (node (ref "XTAL1") (pin "2") (pinfunction "2_2") (pintype "passive"))
      (node (ref "XTAL1") (pin "4") (pinfunction "2_4") (pintype "passive"))
      (node (ref "XTAL2") (pin "2") (pinfunction "2_2") (pintype "passive"))
      (node (ref "XTAL2") (pin "4") (pinfunction "2_4") (pintype "passive"))
    )
    (net (code "3") (name "I2C_SCL") (class "Default")
      (node (ref "IC1") (pin "28") (pinfunction "PC5(ADC5/SCL)_28") (pintype "bidirectional"))
      (node (ref "IC2") (pin "1") (pinfunction "SCL_1") (pintype "bidirectional"))
      (node (ref "IC3") (pin "26") (pinfunction "SCL_26") (pintype "bidirectional"))
      (node (ref "R36") (pin "1") (pinfunction "1_1") (pintype "passive"))
    )
    (net (code "4") (name "I2C_SDA") (class "Default")
      (node (ref "IC1") (pin "27") (pinfunction "PC4(ADC4/SDA)_27") (pintype "bidirectional"))
      (node (ref "IC2") (pin "2") (pinfunction "SDA_2") (pintype "bidirectional"))
      (node (ref "IC3") (pin "27") (pinfunction "SDA_27") (pintype "bidirectional"))
      (node (ref "R35") (pin "2") (pinfunction "2_2") (pintype "passive"))
    )
    (net (code "5") (name "IND_1") (class "Default")
      (node (ref "IC3") (pin "22") (pinfunction "PWM15_22") (pintype "output"))
      (node (ref "R1") (pin "1") (pinfunction "1_1") (pintype "passive"))
    )
    (net (code "6") (name "IND_2") (class "Default")
      (node (ref "IC3") (pin "21") (pinfunction "PWM14_21") (pintype "output"))
      (node (ref "R5") (pin "1") (pinfunction "1_1") (pintype "passive"))
    )
    (net (code "7") (name "IND_3") (class "Default")
      (node (ref "IC3") (pin "20") (pinfunction "PWM13_20") (pintype "output"))
      (node (ref "R9") (pin "1") (pinfunction "1_1") (pintype "passive"))
    )
    (net (code "8") (name "IND_4") (class "Default")
      (node (ref "IC3") (pin "19") (pinfunction "PWM12_19") (pintype "output"))
      (node (ref "R13") (pin "1") (pinfunction "1_1") (pintype "passive"))
    )
    (net (code "9") (name "IND_5") (class "Default")
      (node (ref "IC3") (pin "18") (pinfunction "PWM11_18") (pintype "output"))
      (node (ref "R17") (pin "1") (pinfunction "1_1") (pintype "passive"))
    )
    (net (code "10") (name "IND_6") (class "Default")
      (node (ref "IC3") (pin "17") (pinfunction "PWM10_17") (pintype "output"))
      (node (ref "R21") (pin "1") (pinfunction "1_1") (pintype "passive"))
    )
    (net (code "11") (name "IND_7") (class "Default")
      (node (ref "IC3") (pin "16") (pinfunction "PWM9_16") (pintype "output"))
      (node (ref "R25") (pin "1") (pinfunction "1_1") (pintype "passive"))
    )
    (net (code "12") (name "IND_8") (class "Default")
      (node (ref "IC3") (pin "15") (pinfunction "PWM8_15") (pintype "output"))
      (node (ref "R29") (pin "1") (pinfunction "1_1") (pintype "passive"))
    )
    (net (code "13") (name "INT_BTN") (class "Default")
      (node (ref "IC1") (pin "32") (pinfunction "PD2(INT0)_32") (pintype "bidirectional"))
      (node (ref "IC2") (pin "8") (pinfunction "INT_8") (pintype "bidirectional"))
    )
    (net (code "14") (name "INT_CAN") (class "Default")
      (node (ref "IC1") (pin "1") (pinfunction "PD3(INT1)_1") (pintype "bidirectional"))
      (node (ref "IC4") (pin "4") (pinfunction "INT_4") (pintype "bidirectional"))
    )
    (net (code "15") (name "LED") (class "Default")
      (node (ref "IC1") (pin "12") (pinfunction "PB0(ICP)_12") (pintype "bidirectional"))
      (node (ref "R38") (pin "2") (pinfunction "2_2") (pintype "passive"))
    )
    (net (code "16") (name "Net-(C6-Pad1)") (class "Default")
      (node (ref "C6") (pin "1") (pinfunction "1_1") (pintype "passive"))
      (node (ref "X4") (pin "6") (pinfunction "6_6") (pintype "passive"))
    )
    (net (code "17") (name "Net-(D1-PadA)") (class "Default")
      (node (ref "D1") (pin "A") (pinfunction "A_A") (pintype "passive"))
      (node (ref "R1") (pin "2") (pinfunction "2_2") (pintype "passive"))
    )
    (net (code "18") (name "Net-(D2-PadA)") (class "Default")
      (node (ref "D2") (pin "A") (pinfunction "A_A") (pintype "passive"))
      (node (ref "R5") (pin "2") (pinfunction "2_2") (pintype "passive"))
    )
    (net (code "19") (name "Net-(D3-PadA)") (class "Default")
      (node (ref "D3") (pin "A") (pinfunction "A_A") (pintype "passive"))
      (node (ref "R9") (pin "2") (pinfunction "2_2") (pintype "passive"))
    )
    (net (code "20") (name "Net-(D4-PadA)") (class "Default")
      (node (ref "D4") (pin "A") (pinfunction "A_A") (pintype "passive"))
      (node (ref "R13") (pin "2") (pinfunction "2_2") (pintype "passive"))
    )
    (net (code "21") (name "Net-(D5-PadA)") (class "Default")
      (node (ref "D5") (pin "A") (pinfunction "A_A") (pintype "passive"))
      (node (ref "R17") (pin "2") (pinfunction "2_2") (pintype "passive"))
    )
    (net (code "22") (name "Net-(D6-PadA)") (class "Default")
      (node (ref "D6") (pin "A") (pinfunction "A_A") (pintype "passive"))
      (node (ref "R21") (pin "2") (pinfunction "2_2") (pintype "passive"))
    )
    (net (code "23") (name "Net-(D7-PadA)") (class "Default")
      (node (ref "D7") (pin "A") (pinfunction "A_A") (pintype "passive"))
      (node (ref "R25") (pin "2") (pinfunction "2_2") (pintype "passive"))
    )
    (net (code "24") (name "Net-(D8-PadA)") (class "Default")
      (node (ref "D8") (pin "A") (pinfunction "A_A") (pintype "passive"))
      (node (ref "R29") (pin "2") (pinfunction "2_2") (pintype "passive"))
    )
    (net (code "25") (name "Net-(D9-PadA)") (class "Default")
      (node (ref "D9") (pin "A") (pinfunction "A_A") (pintype "passive"))
      (node (ref "R37") (pin "1") (pinfunction "1_1") (pintype "passive"))
    )
    (net (code "26") (name "Net-(D10-PadA)") (class "Default")
      (node (ref "D10") (pin "A") (pinfunction "A_A") (pintype "passive"))
      (node (ref "R38") (pin "1") (pinfunction "1_1") (pintype "passive"))
    )
    (net (code "27") (name "Net-(D11-PadA)") (class "Default")
      (node (ref "D11") (pin "A") (pinfunction "A_A") (pintype "passive"))
      (node (ref "R39") (pin "1") (pinfunction "1_1") (pintype "passive"))
    )
    (net (code "28") (name "Net-(D12-PadA)") (class "Default")
      (node (ref "D12") (pin "A") (pinfunction "A_A") (pintype "passive"))
      (node (ref "R40") (pin "1") (pinfunction "1_1") (pintype "passive"))
    )
    (net (code "29") (name "Net-(IC1-PB6(XTAL1{slash}TOSC1))") (class "Default")
      (node (ref "C4") (pin "1") (pinfunction "1_1") (pintype "passive"))
      (node (ref "IC1") (pin "7") (pinfunction "PB6(XTAL1/TOSC1)_7") (pintype "bidirectional"))
      (node (ref "XTAL1") (pin "1") (pinfunction "1_1") (pintype "passive"))
    )
    (net (code "30") (name "Net-(IC1-PB7(XTAL2{slash}TOSC2))") (class "Default")
      (node (ref "C5") (pin "1") (pinfunction "1_1") (pintype "passive"))
      (node (ref "IC1") (pin "8") (pinfunction "PB7(XTAL2/TOSC2)_8") (pintype "bidirectional"))
      (node (ref "XTAL1") (pin "3") (pinfunction "3_3") (pintype "passive"))
    )
    (net (code "31") (name "Net-(IC3-#OE)") (class "Default")
      (node (ref "IC3") (pin "23") (pinfunction "#OE_23") (pintype "input"))
      (node (ref "R34") (pin "2") (pinfunction "2_2") (pintype "passive"))
    )
    (net (code "32") (name "Net-(IC4-OSC1)") (class "Default")
      (node (ref "C10") (pin "2") (pinfunction "2_2") (pintype "passive"))
      (node (ref "IC4") (pin "6") (pinfunction "OSC1_6") (pintype "bidirectional"))
      (node (ref "XTAL2") (pin "3") (pinfunction "3_3") (pintype "passive"))
    )
    (net (code "33") (name "Net-(IC4-OSC2)") (class "Default")
      (node (ref "C9") (pin "2") (pinfunction "2_2") (pintype "passive"))
      (node (ref "IC4") (pin "5") (pinfunction "OSC2_5") (pintype "bidirectional"))
      (node (ref "XTAL2") (pin "1") (pinfunction "1_1") (pintype "passive"))
    )
    (net (code "34") (name "Net-(IC4-RXCAN)") (class "Default")
      (node (ref "D12") (pin "C") (pinfunction "C_C") (pintype "passive"))
      (node (ref "IC4") (pin "2") (pinfunction "RXCAN_2") (pintype "bidirectional"))
      (node (ref "IC5") (pin "4") (pinfunction "RXD_4") (pintype "bidirectional"))
    )
    (net (code "35") (name "Net-(IC4-TXCAN)") (class "Default")
      (node (ref "D11") (pin "C") (pinfunction "C_C") (pintype "passive"))
      (node (ref "IC4") (pin "1") (pinfunction "TXCAN_1") (pintype "bidirectional"))
      (node (ref "IC5") (pin "1") (pinfunction "TXD_1") (pintype "bidirectional"))
    )
    (net (code "36") (name "Net-(IC5-CANH)") (class "Default")
      (node (ref "IC5") (pin "7") (pinfunction "CANH_7") (pintype "bidirectional"))
      (node (ref "JP1") (pin "1") (pinfunction "1_1") (pintype "passive"))
      (node (ref "X1") (pin "2") (pinfunction "2_2") (pintype "passive"))
      (node (ref "X2") (pin "2") (pinfunction "2_2") (pintype "passive"))
    )
    (net (code "37") (name "Net-(IC5-CANL)") (class "Default")
      (node (ref "IC5") (pin "6") (pinfunction "CANL_6") (pintype "bidirectional"))
      (node (ref "R43") (pin "1") (pinfunction "1_1") (pintype "passive"))
      (node (ref "X1") (pin "3") (pinfunction "3_3") (pintype "passive"))
      (node (ref "X2") (pin "3") (pinfunction "3_3") (pintype "passive"))
    )
    (net (code "38") (name "Net-(IC6-CB)") (class "Default")
      (node (ref "C14") (pin "1") (pinfunction "1_1") (pintype "passive"))
      (node (ref "IC6") (pin "1") (pinfunction "CB_1") (pintype "bidirectional"))
    )
    (net (code "39") (name "Net-(IC6-FB)") (class "Default")
      (node (ref "IC6") (pin "3") (pinfunction "FB_3") (pintype "bidirectional"))
      (node (ref "R41") (pin "2") (pinfunction "2_2") (pintype "passive"))
      (node (ref "R42") (pin "1") (pinfunction "1_1") (pintype "passive"))
    )
    (net (code "40") (name "Net-(IC6-SW)") (class "Default")
      (node (ref "C14") (pin "2") (pinfunction "2_2") (pintype "passive"))
      (node (ref "IC6") (pin "6") (pinfunction "SW_6") (pintype "bidirectional"))
      (node (ref "L1") (pin "1") (pinfunction "1_1") (pintype "passive"))
    )
    (net (code "41") (name "Net-(JP1-Pad2)") (class "Default")
      (node (ref "JP1") (pin "2") (pinfunction "2_2") (pintype "passive"))
      (node (ref "R43") (pin "2") (pinfunction "2_2") (pintype "passive"))
    )
    (net (code "42") (name "Net-(OK1-A)") (class "Default")
      (node (ref "OK1") (pin "1") (pinfunction "A_1") (pintype "passive"))
      (node (ref "R2") (pin "2") (pinfunction "2_2") (pintype "passive"))
    )
    (net (code "43") (name "Net-(OK1-COL)") (class "Default")
      (node (ref "OK1") (pin "4") (pinfunction "COL_4") (pintype "passive"))
      (node (ref "R3") (pin "2") (pinfunction "2_2") (pintype "passive"))
    )
    (net (code "44") (name "Net-(OK1-EMIT)") (class "Default")
      (node (ref "OK1") (pin "3") (pinfunction "EMIT_3") (pintype "passive"))
      (node (ref "Q1") (pin "1") (pinfunction "G_1") (pintype "passive"))
      (node (ref "R4") (pin "2") (pinfunction "2_2") (pintype "passive"))
    )
    (net (code "45") (name "Net-(OK2-A)") (class "Default")
      (node (ref "OK2") (pin "1") (pinfunction "A_1") (pintype "passive"))
      (node (ref "R6") (pin "2") (pinfunction "2_2") (pintype "passive"))
    )
    (net (code "46") (name "Net-(OK2-COL)") (class "Default")
      (node (ref "OK2") (pin "4") (pinfunction "COL_4") (pintype "passive"))
      (node (ref "R7") (pin "2") (pinfunction "2_2") (pintype "passive"))
    )
    (net (code "47") (name "Net-(OK2-EMIT)") (class "Default")
      (node (ref "OK2") (pin "3") (pinfunction "EMIT_3") (pintype "passive"))
      (node (ref "Q2") (pin "1") (pinfunction "G_1") (pintype "passive"))
      (node (ref "R8") (pin "2") (pinfunction "2_2") (pintype "passive"))
    )
    (net (code "48") (name "Net-(OK3-A)") (class "Default")
      (node (ref "OK3") (pin "1") (pinfunction "A_1") (pintype "passive"))
      (node (ref "R10") (pin "2") (pinfunction "2_2") (pintype "passive"))
    )
    (net (code "49") (name "Net-(OK3-COL)") (class "Default")
      (node (ref "OK3") (pin "4") (pinfunction "COL_4") (pintype "passive"))
      (node (ref "R11") (pin "2") (pinfunction "2_2") (pintype "passive"))
    )
    (net (code "50") (name "Net-(OK3-EMIT)") (class "Default")
      (node (ref "OK3") (pin "3") (pinfunction "EMIT_3") (pintype "passive"))
      (node (ref "Q3") (pin "1") (pinfunction "G_1") (pintype "passive"))
      (node (ref "R12") (pin "2") (pinfunction "2_2") (pintype "passive"))
    )
    (net (code "51") (name "Net-(OK4-A)") (class "Default")
      (node (ref "OK4") (pin "1") (pinfunction "A_1") (pintype "passive"))
      (node (ref "R14") (pin "2") (pinfunction "2_2") (pintype "passive"))
    )
    (net (code "52") (name "Net-(OK4-COL)") (class "Default")
      (node (ref "OK4") (pin "4") (pinfunction "COL_4") (pintype "passive"))
      (node (ref "R15") (pin "2") (pinfunction "2_2") (pintype "passive"))
    )
    (net (code "53") (name "Net-(OK4-EMIT)") (class "Default")
      (node (ref "OK4") (pin "3") (pinfunction "EMIT_3") (pintype "passive"))
      (node (ref "Q4") (pin "1") (pinfunction "G_1") (pintype "passive"))
      (node (ref "R16") (pin "2") (pinfunction "2_2") (pintype "passive"))
    )
    (net (code "54") (name "Net-(OK5-A)") (class "Default")
      (node (ref "OK5") (pin "1") (pinfunction "A_1") (pintype "passive"))
      (node (ref "R18") (pin "2") (pinfunction "2_2") (pintype "passive"))
    )
    (net (code "55") (name "Net-(OK5-COL)") (class "Default")
      (node (ref "OK5") (pin "4") (pinfunction "COL_4") (pintype "passive"))
      (node (ref "R19") (pin "2") (pinfunction "2_2") (pintype "passive"))
    )
    (net (code "56") (name "Net-(OK5-EMIT)") (class "Default")
      (node (ref "OK5") (pin "3") (pinfunction "EMIT_3") (pintype "passive"))
      (node (ref "Q5") (pin "1") (pinfunction "G_1") (pintype "passive"))
      (node (ref "R20") (pin "2") (pinfunction "2_2") (pintype "passive"))
    )
    (net (code "57") (name "Net-(OK6-A)") (class "Default")
      (node (ref "OK6") (pin "1") (pinfunction "A_1") (pintype "passive"))
      (node (ref "R22") (pin "2") (pinfunction "2_2") (pintype "passive"))
    )
    (net (code "58") (name "Net-(OK6-COL)") (class "Default")
      (node (ref "OK6") (pin "4") (pinfunction "COL_4") (pintype "passive"))
      (node (ref "R23") (pin "2") (pinfunction "2_2") (pintype "passive"))
    )
    (net (code "59") (name "Net-(OK6-EMIT)") (class "Default")
      (node (ref "OK6") (pin "3") (pinfunction "EMIT_3") (pintype "passive"))
      (node (ref "Q6") (pin "1") (pinfunction "G_1") (pintype "passive"))
      (node (ref "R24") (pin "2") (pinfunction "2_2") (pintype "passive"))
    )
    (net (code "60") (name "Net-(OK7-A)") (class "Default")
      (node (ref "OK7") (pin "1") (pinfunction "A_1") (pintype "passive"))
      (node (ref "R26") (pin "2") (pinfunction "2_2") (pintype "passive"))
    )
    (net (code "61") (name "Net-(OK7-COL)") (class "Default")
      (node (ref "OK7") (pin "4") (pinfunction "COL_4") (pintype "passive"))
      (node (ref "R27") (pin "2") (pinfunction "2_2") (pintype "passive"))
    )
    (net (code "62") (name "Net-(OK7-EMIT)") (class "Default")
      (node (ref "OK7") (pin "3") (pinfunction "EMIT_3") (pintype "passive"))
      (node (ref "Q7") (pin "1") (pinfunction "G_1") (pintype "passive"))
      (node (ref "R28") (pin "2") (pinfunction "2_2") (pintype "passive"))
    )
    (net (code "63") (name "Net-(OK8-A)") (class "Default")
      (node (ref "OK8") (pin "1") (pinfunction "A_1") (pintype "passive"))
      (node (ref "R30") (pin "2") (pinfunction "2_2") (pintype "passive"))
    )
    (net (code "64") (name "Net-(OK8-COL)") (class "Default")
      (node (ref "OK8") (pin "4") (pinfunction "COL_4") (pintype "passive"))
      (node (ref "R31") (pin "2") (pinfunction "2_2") (pintype "passive"))
    )
    (net (code "65") (name "Net-(OK8-EMIT)") (class "Default")
      (node (ref "OK8") (pin "3") (pinfunction "EMIT_3") (pintype "passive"))
      (node (ref "Q8") (pin "1") (pinfunction "G_1") (pintype "passive"))
      (node (ref "R32") (pin "2") (pinfunction "2_2") (pintype "passive"))
    )
    (net (code "66") (name "Net-(Q1-D-Pad2)") (class "Default")
      (node (ref "Q1") (pin "2") (pinfunction "D_2") (pintype "passive"))
      (node (ref "Q1") (pin "4") (pinfunction "D_4") (pintype "passive"))
      (node (ref "X10") (pin "1") (pinfunction "PIN_1") (pintype "bidirectional"))
      (node (ref "X10") (pin "2") (pinfunction "PIN_2") (pintype "bidirectional"))
      (node (ref "X10") (pin "3") (pinfunction "PIN_3") (pintype "bidirectional"))
      (node (ref "X10") (pin "4") (pinfunction "PIN_4") (pintype "bidirectional"))
    )
    (net (code "67") (name "Net-(Q1-S)") (class "Default")
      (node (ref "Q1") (pin "3") (pinfunction "S_3") (pintype "passive"))
      (node (ref "R4") (pin "1") (pinfunction "1_1") (pintype "passive"))
      (node (ref "X8") (pin "1") (pinfunction "PIN_1") (pintype "bidirectional"))
      (node (ref "X8") (pin "2") (pinfunction "PIN_2") (pintype "bidirectional"))
      (node (ref "X8") (pin "3") (pinfunction "PIN_3") (pintype "bidirectional"))
      (node (ref "X8") (pin "4") (pinfunction "PIN_4") (pintype "bidirectional"))
    )
    (net (code "68") (name "Net-(Q2-D-Pad2)") (class "Default")
      (node (ref "Q2") (pin "2") (pinfunction "D_2") (pintype "passive"))
      (node (ref "Q2") (pin "4") (pinfunction "D_4") (pintype "passive"))
      (node (ref "X18") (pin "1") (pinfunction "PIN_1") (pintype "bidirectional"))
      (node (ref "X18") (pin "2") (pinfunction "PIN_2") (pintype "bidirectional"))
      (node (ref "X18") (pin "3") (pinfunction "PIN_3") (pintype "bidirectional"))
      (node (ref "X18") (pin "4") (pinfunction "PIN_4") (pintype "bidirectional"))
    )
    (net (code "69") (name "Net-(Q2-S)") (class "Default")
      (node (ref "Q2") (pin "3") (pinfunction "S_3") (pintype "passive"))
      (node (ref "R8") (pin "1") (pinfunction "1_1") (pintype "passive"))
      (node (ref "X16") (pin "1") (pinfunction "PIN_1") (pintype "bidirectional"))
      (node (ref "X16") (pin "2") (pinfunction "PIN_2") (pintype "bidirectional"))
      (node (ref "X16") (pin "3") (pinfunction "PIN_3") (pintype "bidirectional"))
      (node (ref "X16") (pin "4") (pinfunction "PIN_4") (pintype "bidirectional"))
    )
    (net (code "70") (name "Net-(Q3-D-Pad2)") (class "Default")
      (node (ref "Q3") (pin "2") (pinfunction "D_2") (pintype "passive"))
      (node (ref "Q3") (pin "4") (pinfunction "D_4") (pintype "passive"))
      (node (ref "X14") (pin "1") (pinfunction "PIN_1") (pintype "bidirectional"))
      (node (ref "X14") (pin "2") (pinfunction "PIN_2") (pintype "bidirectional"))
      (node (ref "X14") (pin "3") (pinfunction "PIN_3") (pintype "bidirectional"))
      (node (ref "X14") (pin "4") (pinfunction "PIN_4") (pintype "bidirectional"))
    )
    (net (code "71") (name "Net-(Q3-S)") (class "Default")
      (node (ref "Q3") (pin "3") (pinfunction "S_3") (pintype "passive"))
      (node (ref "R12") (pin "1") (pinfunction "1_1") (pintype "passive"))
      (node (ref "X12") (pin "1") (pinfunction "PIN_1") (pintype "bidirectional"))
      (node (ref "X12") (pin "2") (pinfunction "PIN_2") (pintype "bidirectional"))
      (node (ref "X12") (pin "3") (pinfunction "PIN_3") (pintype "bidirectional"))
      (node (ref "X12") (pin "4") (pinfunction "PIN_4") (pintype "bidirectional"))
    )
    (net (code "72") (name "Net-(Q4-D-Pad2)") (class "Default")
      (node (ref "Q4") (pin "2") (pinfunction "D_2") (pintype "passive"))
      (node (ref "Q4") (pin "4") (pinfunction "D_4") (pintype "passive"))
      (node (ref "X26") (pin "1") (pinfunction "PIN_1") (pintype "bidirectional"))
      (node (ref "X26") (pin "2") (pinfunction "PIN_2") (pintype "bidirectional"))
      (node (ref "X26") (pin "3") (pinfunction "PIN_3") (pintype "bidirectional"))
      (node (ref "X26") (pin "4") (pinfunction "PIN_4") (pintype "bidirectional"))
    )
    (net (code "73") (name "Net-(Q4-S)") (class "Default")
      (node (ref "Q4") (pin "3") (pinfunction "S_3") (pintype "passive"))
      (node (ref "R16") (pin "1") (pinfunction "1_1") (pintype "passive"))
      (node (ref "X24") (pin "1") (pinfunction "PIN_1") (pintype "bidirectional"))
      (node (ref "X24") (pin "2") (pinfunction "PIN_2") (pintype "bidirectional"))
      (node (ref "X24") (pin "3") (pinfunction "PIN_3") (pintype "bidirectional"))
      (node (ref "X24") (pin "4") (pinfunction "PIN_4") (pintype "bidirectional"))
    )
    (net (code "74") (name "Net-(Q5-D-Pad2)") (class "Default")
      (node (ref "Q5") (pin "2") (pinfunction "D_2") (pintype "passive"))
      (node (ref "Q5") (pin "4") (pinfunction "D_4") (pintype "passive"))
      (node (ref "X22") (pin "1") (pinfunction "PIN_1") (pintype "bidirectional"))
      (node (ref "X22") (pin "2") (pinfunction "PIN_2") (pintype "bidirectional"))
      (node (ref "X22") (pin "3") (pinfunction "PIN_3") (pintype "bidirectional"))
      (node (ref "X22") (pin "4") (pinfunction "PIN_4") (pintype "bidirectional"))
    )
    (net (code "75") (name "Net-(Q5-S)") (class "Default")
      (node (ref "Q5") (pin "3") (pinfunction "S_3") (pintype "passive"))
      (node (ref "R20") (pin "1") (pinfunction "1_1") (pintype "passive"))
      (node (ref "X20") (pin "1") (pinfunction "PIN_1") (pintype "bidirectional"))
      (node (ref "X20") (pin "2") (pinfunction "PIN_2") (pintype "bidirectional"))
      (node (ref "X20") (pin "3") (pinfunction "PIN_3") (pintype "bidirectional"))
      (node (ref "X20") (pin "4") (pinfunction "PIN_4") (pintype "bidirectional"))
    )
    (net (code "76") (name "Net-(Q6-D-Pad2)") (class "Default")
      (node (ref "Q6") (pin "2") (pinfunction "D_2") (pintype "passive"))
      (node (ref "Q6") (pin "4") (pinfunction "D_4") (pintype "passive"))
      (node (ref "X30") (pin "1") (pinfunction "PIN_1") (pintype "bidirectional"))
      (node (ref "X30") (pin "2") (pinfunction "PIN_2") (pintype "bidirectional"))
      (node (ref "X30") (pin "3") (pinfunction "PIN_3") (pintype "bidirectional"))
      (node (ref "X30") (pin "4") (pinfunction "PIN_4") (pintype "bidirectional"))
    )
    (net (code "77") (name "Net-(Q6-S)") (class "Default")
      (node (ref "Q6") (pin "3") (pinfunction "S_3") (pintype "passive"))
      (node (ref "R24") (pin "1") (pinfunction "1_1") (pintype "passive"))
      (node (ref "X28") (pin "1") (pinfunction "PIN_1") (pintype "bidirectional"))
      (node (ref "X28") (pin "2") (pinfunction "PIN_2") (pintype "bidirectional"))
      (node (ref "X28") (pin "3") (pinfunction "PIN_3") (pintype "bidirectional"))
      (node (ref "X28") (pin "4") (pinfunction "PIN_4") (pintype "bidirectional"))
    )
    (net (code "78") (name "Net-(Q7-D-Pad2)") (class "Default")
      (node (ref "Q7") (pin "2") (pinfunction "D_2") (pintype "passive"))
      (node (ref "Q7") (pin "4") (pinfunction "D_4") (pintype "passive"))
      (node (ref "X38") (pin "1") (pinfunction "PIN_1") (pintype "bidirectional"))
      (node (ref "X38") (pin "2") (pinfunction "PIN_2") (pintype "bidirectional"))
      (node (ref "X38") (pin "3") (pinfunction "PIN_3") (pintype "bidirectional"))
      (node (ref "X38") (pin "4") (pinfunction "PIN_4") (pintype "bidirectional"))
    )
    (net (code "79") (name "Net-(Q7-S)") (class "Default")
      (node (ref "Q7") (pin "3") (pinfunction "S_3") (pintype "passive"))
      (node (ref "R28") (pin "1") (pinfunction "1_1") (pintype "passive"))
      (node (ref "X36") (pin "1") (pinfunction "PIN_1") (pintype "bidirectional"))
      (node (ref "X36") (pin "2") (pinfunction "PIN_2") (pintype "bidirectional"))
      (node (ref "X36") (pin "3") (pinfunction "PIN_3") (pintype "bidirectional"))
      (node (ref "X36") (pin "4") (pinfunction "PIN_4") (pintype "bidirectional"))
    )
    (net (code "80") (name "Net-(Q8-D-Pad2)") (class "Default")
      (node (ref "Q8") (pin "2") (pinfunction "D_2") (pintype "passive"))
      (node (ref "Q8") (pin "4") (pinfunction "D_4") (pintype "passive"))
      (node (ref "X46") (pin "1") (pinfunction "PIN_1") (pintype "bidirectional"))
      (node (ref "X46") (pin "2") (pinfunction "PIN_2") (pintype "bidirectional"))
      (node (ref "X46") (pin "3") (pinfunction "PIN_3") (pintype "bidirectional"))
      (node (ref "X46") (pin "4") (pinfunction "PIN_4") (pintype "bidirectional"))
    )
    (net (code "81") (name "Net-(Q8-S)") (class "Default")
      (node (ref "Q8") (pin "3") (pinfunction "S_3") (pintype "passive"))
      (node (ref "R32") (pin "1") (pinfunction "1_1") (pintype "passive"))
      (node (ref "X44") (pin "1") (pinfunction "PIN_1") (pintype "bidirectional"))
      (node (ref "X44") (pin "2") (pinfunction "PIN_2") (pintype "bidirectional"))
      (node (ref "X44") (pin "3") (pinfunction "PIN_3") (pintype "bidirectional"))
      (node (ref "X44") (pin "4") (pinfunction "PIN_4") (pintype "bidirectional"))
    )
    (net (code "82") (name "Net-(R3-Pad1)") (class "Default")
      (node (ref "R3") (pin "1") (pinfunction "1_1") (pintype "passive"))
      (node (ref "X7") (pin "1") (pinfunction "PIN_1") (pintype "bidirectional"))
      (node (ref "X7") (pin "2") (pinfunction "PIN_2") (pintype "bidirectional"))
      (node (ref "X7") (pin "3") (pinfunction "PIN_3") (pintype "bidirectional"))
      (node (ref "X7") (pin "4") (pinfunction "PIN_4") (pintype "bidirectional"))
      (node (ref "X9") (pin "1") (pinfunction "PIN_1") (pintype "bidirectional"))
      (node (ref "X9") (pin "2") (pinfunction "PIN_2") (pintype "bidirectional"))
      (node (ref "X9") (pin "3") (pinfunction "PIN_3") (pintype "bidirectional"))
      (node (ref "X9") (pin "4") (pinfunction "PIN_4") (pintype "bidirectional"))
    )
    (net (code "83") (name "Net-(R7-Pad1)") (class "Default")
      (node (ref "R7") (pin "1") (pinfunction "1_1") (pintype "passive"))
      (node (ref "X15") (pin "1") (pinfunction "PIN_1") (pintype "bidirectional"))
      (node (ref "X15") (pin "2") (pinfunction "PIN_2") (pintype "bidirectional"))
      (node (ref "X15") (pin "3") (pinfunction "PIN_3") (pintype "bidirectional"))
      (node (ref "X15") (pin "4") (pinfunction "PIN_4") (pintype "bidirectional"))
      (node (ref "X17") (pin "1") (pinfunction "PIN_1") (pintype "bidirectional"))
      (node (ref "X17") (pin "2") (pinfunction "PIN_2") (pintype "bidirectional"))
      (node (ref "X17") (pin "3") (pinfunction "PIN_3") (pintype "bidirectional"))
      (node (ref "X17") (pin "4") (pinfunction "PIN_4") (pintype "bidirectional"))
    )
    (net (code "84") (name "Net-(R11-Pad1)") (class "Default")
      (node (ref "R11") (pin "1") (pinfunction "1_1") (pintype "passive"))
      (node (ref "X11") (pin "1") (pinfunction "PIN_1") (pintype "bidirectional"))
      (node (ref "X11") (pin "2") (pinfunction "PIN_2") (pintype "bidirectional"))
      (node (ref "X11") (pin "3") (pinfunction "PIN_3") (pintype "bidirectional"))
      (node (ref "X11") (pin "4") (pinfunction "PIN_4") (pintype "bidirectional"))
      (node (ref "X13") (pin "1") (pinfunction "PIN_1") (pintype "bidirectional"))
      (node (ref "X13") (pin "2") (pinfunction "PIN_2") (pintype "bidirectional"))
      (node (ref "X13") (pin "3") (pinfunction "PIN_3") (pintype "bidirectional"))
      (node (ref "X13") (pin "4") (pinfunction "PIN_4") (pintype "bidirectional"))
    )
    (net (code "85") (name "Net-(R15-Pad1)") (class "Default")
      (node (ref "R15") (pin "1") (pinfunction "1_1") (pintype "passive"))
      (node (ref "X23") (pin "1") (pinfunction "PIN_1") (pintype "bidirectional"))
      (node (ref "X23") (pin "2") (pinfunction "PIN_2") (pintype "bidirectional"))
      (node (ref "X23") (pin "3") (pinfunction "PIN_3") (pintype "bidirectional"))
      (node (ref "X23") (pin "4") (pinfunction "PIN_4") (pintype "bidirectional"))
      (node (ref "X25") (pin "1") (pinfunction "PIN_1") (pintype "bidirectional"))
      (node (ref "X25") (pin "2") (pinfunction "PIN_2") (pintype "bidirectional"))
      (node (ref "X25") (pin "3") (pinfunction "PIN_3") (pintype "bidirectional"))
      (node (ref "X25") (pin "4") (pinfunction "PIN_4") (pintype "bidirectional"))
    )
    (net (code "86") (name "Net-(R19-Pad1)") (class "Default")
      (node (ref "R19") (pin "1") (pinfunction "1_1") (pintype "passive"))
      (node (ref "X19") (pin "1") (pinfunction "PIN_1") (pintype "bidirectional"))
      (node (ref "X19") (pin "2") (pinfunction "PIN_2") (pintype "bidirectional"))
      (node (ref "X19") (pin "3") (pinfunction "PIN_3") (pintype "bidirectional"))
      (node (ref "X19") (pin "4") (pinfunction "PIN_4") (pintype "bidirectional"))
      (node (ref "X21") (pin "1") (pinfunction "PIN_1") (pintype "bidirectional"))
      (node (ref "X21") (pin "2") (pinfunction "PIN_2") (pintype "bidirectional"))
      (node (ref "X21") (pin "3") (pinfunction "PIN_3") (pintype "bidirectional"))
      (node (ref "X21") (pin "4") (pinfunction "PIN_4") (pintype "bidirectional"))
    )
    (net (code "87") (name "Net-(R23-Pad1)") (class "Default")
      (node (ref "R23") (pin "1") (pinfunction "1_1") (pintype "passive"))
      (node (ref "X27") (pin "1") (pinfunction "PIN_1") (pintype "bidirectional"))
      (node (ref "X27") (pin "2") (pinfunction "PIN_2") (pintype "bidirectional"))
      (node (ref "X27") (pin "3") (pinfunction "PIN_3") (pintype "bidirectional"))
      (node (ref "X27") (pin "4") (pinfunction "PIN_4") (pintype "bidirectional"))
      (node (ref "X29") (pin "1") (pinfunction "PIN_1") (pintype "bidirectional"))
      (node (ref "X29") (pin "2") (pinfunction "PIN_2") (pintype "bidirectional"))
      (node (ref "X29") (pin "3") (pinfunction "PIN_3") (pintype "bidirectional"))
      (node (ref "X29") (pin "4") (pinfunction "PIN_4") (pintype "bidirectional"))
    )
    (net (code "88") (name "Net-(R27-Pad1)") (class "Default")
      (node (ref "R27") (pin "1") (pinfunction "1_1") (pintype "passive"))
      (node (ref "X35") (pin "1") (pinfunction "PIN_1") (pintype "bidirectional"))
      (node (ref "X35") (pin "2") (pinfunction "PIN_2") (pintype "bidirectional"))
      (node (ref "X35") (pin "3") (pinfunction "PIN_3") (pintype "bidirectional"))
      (node (ref "X35") (pin "4") (pinfunction "PIN_4") (pintype "bidirectional"))
      (node (ref "X37") (pin "1") (pinfunction "PIN_1") (pintype "bidirectional"))
      (node (ref "X37") (pin "2") (pinfunction "PIN_2") (pintype "bidirectional"))
      (node (ref "X37") (pin "3") (pinfunction "PIN_3") (pintype "bidirectional"))
      (node (ref "X37") (pin "4") (pinfunction "PIN_4") (pintype "bidirectional"))
    )
    (net (code "89") (name "Net-(R31-Pad1)") (class "Default")
      (node (ref "R31") (pin "1") (pinfunction "1_1") (pintype "passive"))
      (node (ref "X43") (pin "1") (pinfunction "PIN_1") (pintype "bidirectional"))
      (node (ref "X43") (pin "2") (pinfunction "PIN_2") (pintype "bidirectional"))
      (node (ref "X43") (pin "3") (pinfunction "PIN_3") (pintype "bidirectional"))
      (node (ref "X43") (pin "4") (pinfunction "PIN_4") (pintype "bidirectional"))
      (node (ref "X45") (pin "1") (pinfunction "PIN_1") (pintype "bidirectional"))
      (node (ref "X45") (pin "2") (pinfunction "PIN_2") (pintype "bidirectional"))
      (node (ref "X45") (pin "3") (pinfunction "PIN_3") (pintype "bidirectional"))
      (node (ref "X45") (pin "4") (pinfunction "PIN_4") (pintype "bidirectional"))
    )
    (net (code "90") (name "OPTO_1") (class "Default")
      (node (ref "IC3") (pin "6") (pinfunction "PWM0_6") (pintype "output"))
      (node (ref "R2") (pin "1") (pinfunction "1_1") (pintype "passive"))
    )
    (net (code "91") (name "OPTO_2") (class "Default")
      (node (ref "IC3") (pin "7") (pinfunction "PWM1_7") (pintype "output"))
      (node (ref "R6") (pin "1") (pinfunction "1_1") (pintype "passive"))
    )
    (net (code "92") (name "OPTO_3") (class "Default")
      (node (ref "IC3") (pin "8") (pinfunction "PWM2_8") (pintype "output"))
      (node (ref "R10") (pin "1") (pinfunction "1_1") (pintype "passive"))
    )
    (net (code "93") (name "OPTO_4") (class "Default")
      (node (ref "IC3") (pin "9") (pinfunction "PWM3_9") (pintype "output"))
      (node (ref "R14") (pin "1") (pinfunction "1_1") (pintype "passive"))
    )
    (net (code "94") (name "OPTO_5") (class "Default")
      (node (ref "IC3") (pin "10") (pinfunction "PWM4_10") (pintype "output"))
      (node (ref "R18") (pin "1") (pinfunction "1_1") (pintype "passive"))
    )
    (net (code "95") (name "OPTO_6") (class "Default")
      (node (ref "IC3") (pin "11") (pinfunction "PWM5_11") (pintype "output"))
      (node (ref "R22") (pin "1") (pinfunction "1_1") (pintype "passive"))
    )
    (net (code "96") (name "OPTO_7") (class "Default")
      (node (ref "IC3") (pin "12") (pinfunction "PWM6_12") (pintype "output"))
      (node (ref "R26") (pin "1") (pinfunction "1_1") (pintype "passive"))
    )
    (net (code "97") (name "OPTO_8") (class "Default")
      (node (ref "IC3") (pin "13") (pinfunction "PWM7_13") (pintype "output"))
      (node (ref "R30") (pin "1") (pinfunction "1_1") (pintype "passive"))
    )
    (net (code "98") (name "RESET") (class "Default")
      (node (ref "C6") (pin "2") (pinfunction "2_2") (pintype "passive"))
      (node (ref "IC1") (pin "29") (pinfunction "PC6(/RESET)_29") (pintype "bidirectional"))
      (node (ref "IC2") (pin "6") (pinfunction "RESET_6") (pintype "bidirectional"))
      (node (ref "R33") (pin "1") (pinfunction "1_1") (pintype "passive"))
      (node (ref "S9") (pin "B1") (pinfunction "2_B1") (pintype "passive"))
      (node (ref "S9") (pin "B2") (pinfunction "2_B2") (pintype "passive"))
      (node (ref "X3") (pin "5") (pinfunction "5_5") (pintype "passive"))
    )
    (net (code "99") (name "SEL_1") (class "Default")
      (node (ref "IC2") (pin "17") (pinfunction "GPIO7_17") (pintype "bidirectional"))
      (node (ref "S1") (pin "A1") (pinfunction "1_A1") (pintype "passive"))
      (node (ref "S1") (pin "A2") (pinfunction "1_A2") (pintype "passive"))
    )
    (net (code "100") (name "SEL_2") (class "Default")
      (node (ref "IC2") (pin "16") (pinfunction "GPIO6_16") (pintype "bidirectional"))
      (node (ref "S2") (pin "A1") (pinfunction "1_A1") (pintype "passive"))
      (node (ref "S2") (pin "A2") (pinfunction "1_A2") (pintype "passive"))
    )
    (net (code "101") (name "SEL_3") (class "Default")
      (node (ref "IC2") (pin "15") (pinfunction "GPIO5_15") (pintype "bidirectional"))
      (node (ref "S3") (pin "A1") (pinfunction "1_A1") (pintype "passive"))
      (node (ref "S3") (pin "A2") (pinfunction "1_A2") (pintype "passive"))
    )
    (net (code "102") (name "SEL_4") (class "Default")
      (node (ref "IC2") (pin "14") (pinfunction "GPIO4_14") (pintype "bidirectional"))
      (node (ref "S4") (pin "A1") (pinfunction "1_A1") (pintype "passive"))
      (node (ref "S4") (pin "A2") (pinfunction "1_A2") (pintype "passive"))
    )
    (net (code "103") (name "SEL_5") (class "Default")
      (node (ref "IC2") (pin "13") (pinfunction "GPIO3_13") (pintype "bidirectional"))
      (node (ref "S5") (pin "A1") (pinfunction "1_A1") (pintype "passive"))
      (node (ref "S5") (pin "A2") (pinfunction "1_A2") (pintype "passive"))
    )
    (net (code "104") (name "SEL_6") (class "Default")
      (node (ref "IC2") (pin "12") (pinfunction "GPIO2_12") (pintype "bidirectional"))
      (node (ref "S6") (pin "A1") (pinfunction "1_A1") (pintype "passive"))
      (node (ref "S6") (pin "A2") (pinfunction "1_A2") (pintype "passive"))
    )
    (net (code "105") (name "SEL_7") (class "Default")
      (node (ref "IC2") (pin "11") (pinfunction "GPIO1_11") (pintype "bidirectional"))
      (node (ref "S7") (pin "A1") (pinfunction "1_A1") (pintype "passive"))
      (node (ref "S7") (pin "A2") (pinfunction "1_A2") (pintype "passive"))
    )
    (net (code "106") (name "SEL_8") (class "Default")
      (node (ref "IC2") (pin "10") (pinfunction "GPIO0_10") (pintype "bidirectional"))
      (node (ref "S8") (pin "A1") (pinfunction "1_A1") (pintype "passive"))
      (node (ref "S8") (pin "A2") (pinfunction "1_A2") (pintype "passive"))
    )
    (net (code "107") (name "SPI_CLK") (class "Default")
      (node (ref "IC1") (pin "17") (pinfunction "PB5(SCK)_17") (pintype "bidirectional"))
      (node (ref "IC4") (pin "10") (pinfunction "SCK_10") (pintype "bidirectional"))
      (node (ref "X3") (pin "3") (pinfunction "3_3") (pintype "passive"))
    )
    (net (code "108") (name "SPI_CS_CAN") (class "Default")
      (node (ref "IC1") (pin "14") (pinfunction "PB2(SS/OC1B)_14") (pintype "bidirectional"))
      (node (ref "IC4") (pin "13") (pinfunction "CS_13") (pintype "bidirectional"))
    )
    (net (code "109") (name "SPI_MISO") (class "Default")
      (node (ref "IC1") (pin "16") (pinfunction "PB4(MISO)_16") (pintype "bidirectional"))
      (node (ref "IC4") (pin "12") (pinfunction "SDO_12") (pintype "bidirectional"))
      (node (ref "X3") (pin "1") (pinfunction "1_1") (pintype "passive"))
    )
    (net (code "110") (name "SPI_MOSI") (class "Default")
      (node (ref "IC1") (pin "15") (pinfunction "PB3(MOSI/OC2)_15") (pintype "bidirectional"))
      (node (ref "IC4") (pin "11") (pinfunction "SDI_11") (pintype "bidirectional"))
      (node (ref "X3") (pin "4") (pinfunction "4_4") (pintype "passive"))
    )
    (net (code "111") (name "UART_RX") (class "Default")
      (node (ref "IC1") (pin "30") (pinfunction "PD0(RXD)_30") (pintype "bidirectional"))
      (node (ref "X4") (pin "4") (pinfunction "4_4") (pintype "passive"))
    )
    (net (code "112") (name "UART_TX") (class "Default")
      (node (ref "IC1") (pin "31") (pinfunction "PD1(TXD)_31") (pintype "bidirectional"))
      (node (ref "X4") (pin "5") (pinfunction "5_5") (pintype "passive"))
    )
    (net (code "113") (name "VCC") (class "Default")
      (node (ref "C1") (pin "1") (pinfunction "1_1") (pintype "passive"))
      (node (ref "C11") (pin "1") (pinfunction "1_1") (pintype "passive"))
      (node (ref "C12") (pin "2") (pinfunction "2_2") (pintype "passive"))
      (node (ref "C13") (pin "2") (pinfunction "2_2") (pintype "passive"))
      (node (ref "C2") (pin "1") (pinfunction "1_1") (pintype "passive"))
      (node (ref "C3") (pin "1") (pinfunction "1_1") (pintype "passive"))
      (node (ref "C7") (pin "2") (pinfunction "2_2") (pintype "passive"))
      (node (ref "C8") (pin "1") (pinfunction "1_1") (pintype "passive"))
      (node (ref "IC1") (pin "18") (pinfunction "AVCC_18") (pintype "bidirectional"))
      (node (ref "IC1") (pin "20") (pinfunction "AREF_20") (pintype "bidirectional"))
      (node (ref "IC1") (pin "4") (pinfunction "VCC_4") (pintype "bidirectional"))
      (node (ref "IC1") (pin "6") (pinfunction "VCC_6") (pintype "bidirectional"))
      (node (ref "IC2") (pin "18") (pinfunction "VCC_18") (pintype "bidirectional"))
      (node (ref "IC3") (pin "28") (pinfunction "VDD_28") (pintype "power_in"))
      (node (ref "IC4") (pin "14") (pinfunction "VCC_14") (pintype "bidirectional"))
      (node (ref "IC5") (pin "3") (pinfunction "VCC_3") (pintype "bidirectional"))
      (node (ref "IC5") (pin "5") (pinfunction "VIO_5") (pintype "bidirectional"))
      (node (ref "L1") (pin "2") (pinfunction "2_2") (pintype "passive"))
      (node (ref "R33") (pin "2") (pinfunction "2_2") (pintype "passive"))
      (node (ref "R35") (pin "1") (pinfunction "1_1") (pintype "passive"))
      (node (ref "R36") (pin "2") (pinfunction "2_2") (pintype "passive"))
      (node (ref "R37") (pin "2") (pinfunction "2_2") (pintype "passive"))
      (node (ref "R39") (pin "2") (pinfunction "2_2") (pintype "passive"))
      (node (ref "R40") (pin "2") (pinfunction "2_2") (pintype "passive"))
      (node (ref "R42") (pin "2") (pinfunction "2_2") (pintype "passive"))
      (node (ref "X3") (pin "2") (pinfunction "2_2") (pintype "passive"))
      (node (ref "X4") (pin "3") (pinfunction "3_3") (pintype "passive"))
    )
    (net (code "114") (name "unconnected-(IC1-ADC6-Pad19)") (class "Default")
      (node (ref "IC1") (pin "19") (pinfunction "ADC6_19") (pintype "bidirectional"))
    )
    (net (code "115") (name "unconnected-(IC1-ADC7-Pad22)") (class "Default")
      (node (ref "IC1") (pin "22") (pinfunction "ADC7_22") (pintype "bidirectional"))
    )
    (net (code "116") (name "unconnected-(IC1-PB1(OC1A)-Pad13)") (class "Default")
      (node (ref "IC1") (pin "13") (pinfunction "PB1(OC1A)_13") (pintype "bidirectional"))
    )
    (net (code "117") (name "unconnected-(IC1-PC0(ADC0)-Pad23)") (class "Default")
      (node (ref "IC1") (pin "23") (pinfunction "PC0(ADC0)_23") (pintype "bidirectional"))
    )
    (net (code "118") (name "unconnected-(IC1-PC1(ADC1)-Pad24)") (class "Default")
      (node (ref "IC1") (pin "24") (pinfunction "PC1(ADC1)_24") (pintype "bidirectional"))
    )
    (net (code "119") (name "unconnected-(IC1-PC2(ADC2)-Pad25)") (class "Default")
      (node (ref "IC1") (pin "25") (pinfunction "PC2(ADC2)_25") (pintype "bidirectional"))
    )
    (net (code "120") (name "unconnected-(IC1-PC3(ADC3)-Pad26)") (class "Default")
      (node (ref "IC1") (pin "26") (pinfunction "PC3(ADC3)_26") (pintype "bidirectional"))
    )
    (net (code "121") (name "unconnected-(IC1-PD4(XCK{slash}T0)-Pad2)") (class "Default")
      (node (ref "IC1") (pin "2") (pinfunction "PD4(XCK/T0)_2") (pintype "bidirectional"))
    )
    (net (code "122") (name "unconnected-(IC1-PD5(T1)-Pad9)") (class "Default")
      (node (ref "IC1") (pin "9") (pinfunction "PD5(T1)_9") (pintype "bidirectional"))
    )
    (net (code "123") (name "unconnected-(IC1-PD6(AIN0)-Pad10)") (class "Default")
      (node (ref "IC1") (pin "10") (pinfunction "PD6(AIN0)_10") (pintype "bidirectional"))
    )
    (net (code "124") (name "unconnected-(IC1-PD7(AIN1)-Pad11)") (class "Default")
      (node (ref "IC1") (pin "11") (pinfunction "PD7(AIN1)_11") (pintype "bidirectional"))
    )
    (net (code "125") (name "unconnected-(IC4-CLKO{slash}SOF-Pad3)") (class "Default")
      (node (ref "IC4") (pin "3") (pinfunction "CLKO/SOF_3") (pintype "bidirectional"))
    )
    (net (code "126") (name "unconnected-(IC4-GPIO0-Pad9)") (class "Default")
      (node (ref "IC4") (pin "9") (pinfunction "GPIO0_9") (pintype "bidirectional"))
    )
    (net (code "127") (name "unconnected-(IC4-GPIO1-Pad8)") (class "Default")
      (node (ref "IC4") (pin "8") (pinfunction "GPIO1_8") (pintype "bidirectional"))
    )
  )
)
